# CN-Cape-1_1.net
KiCad netlist of a schematic drawn in EAGLE
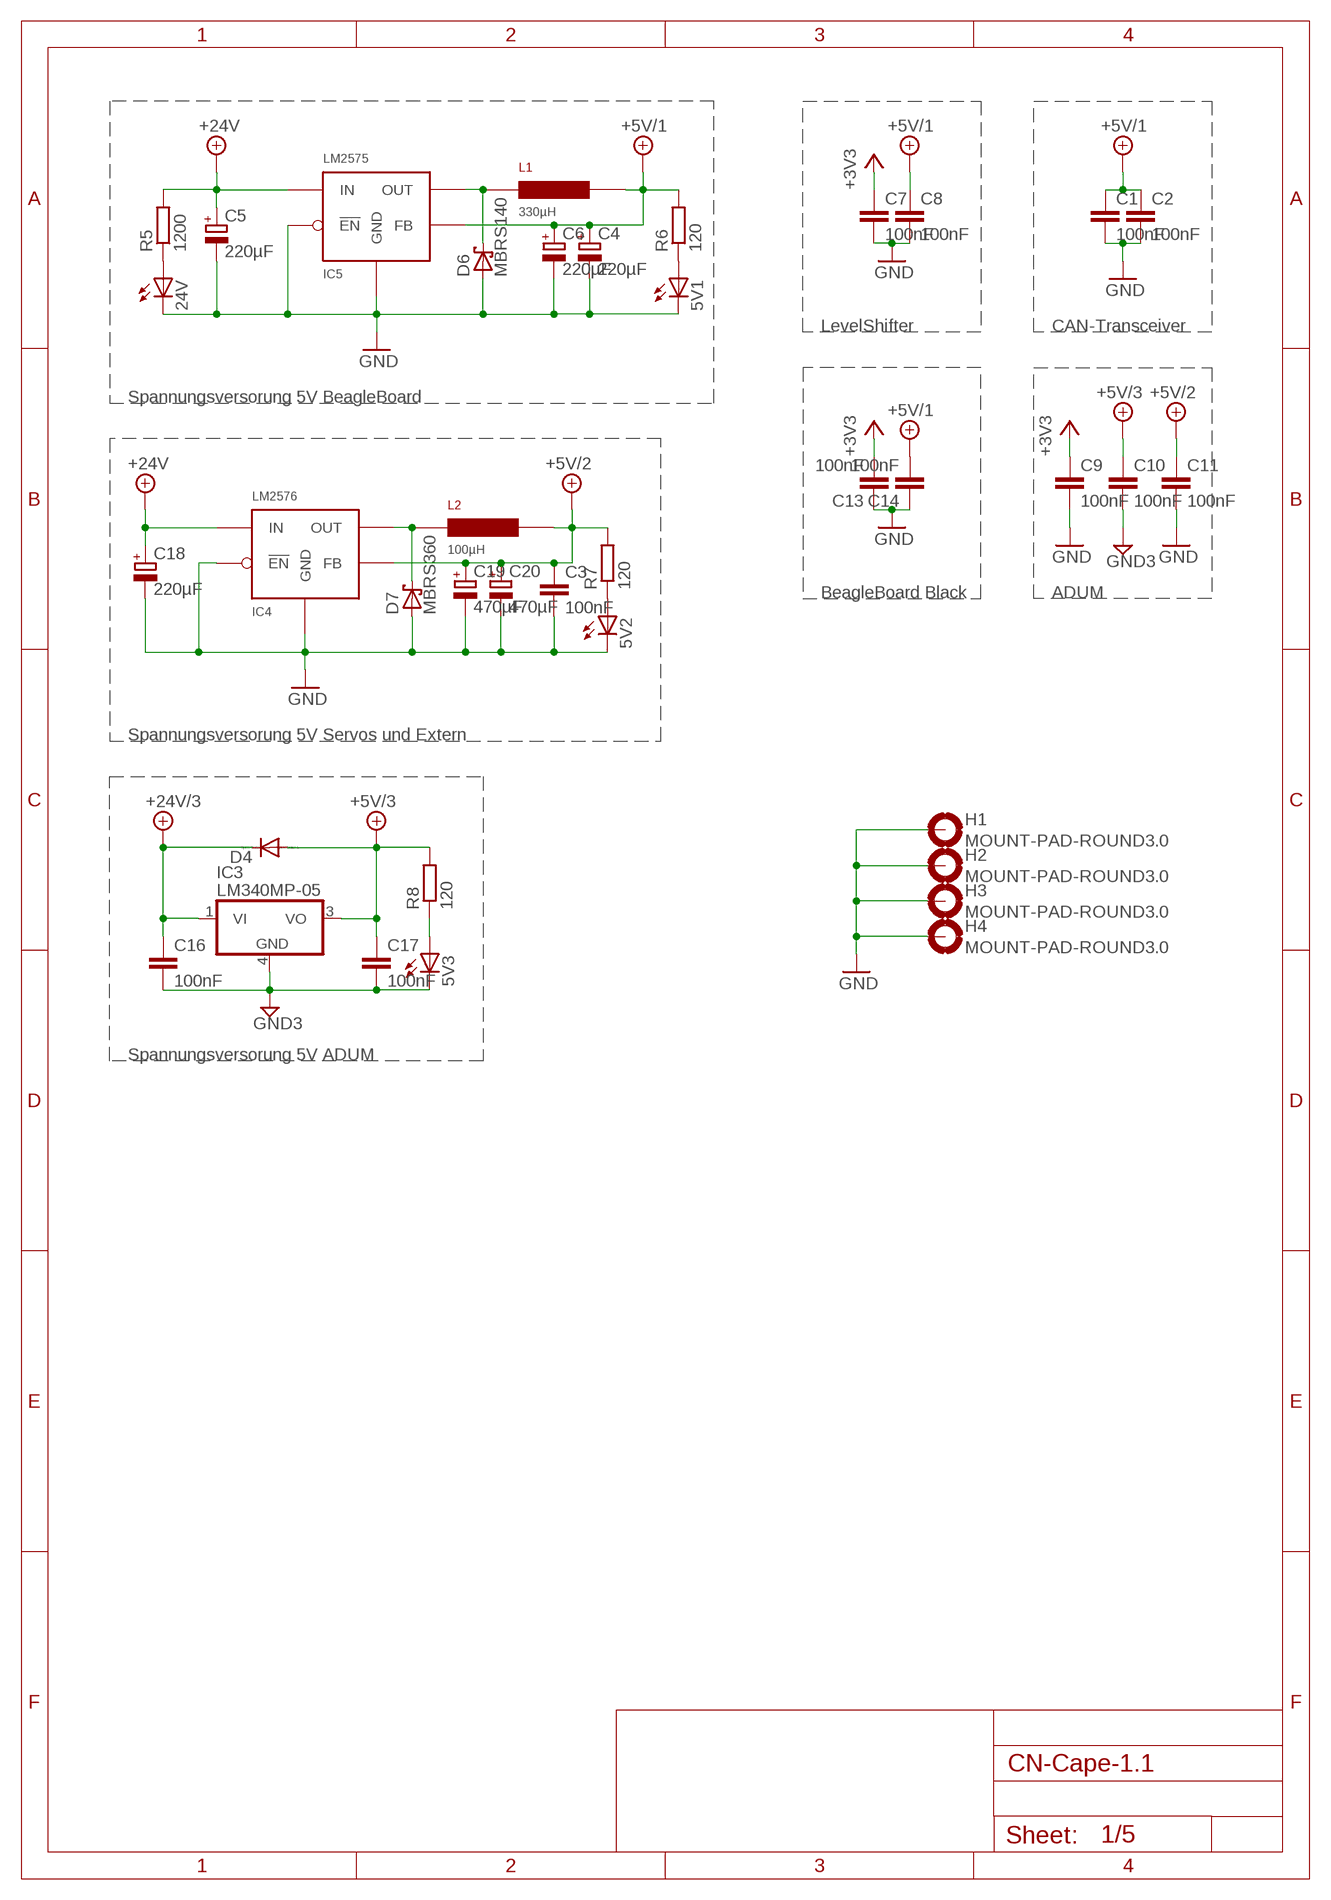
[diagram p0: schematic, sheet 1]
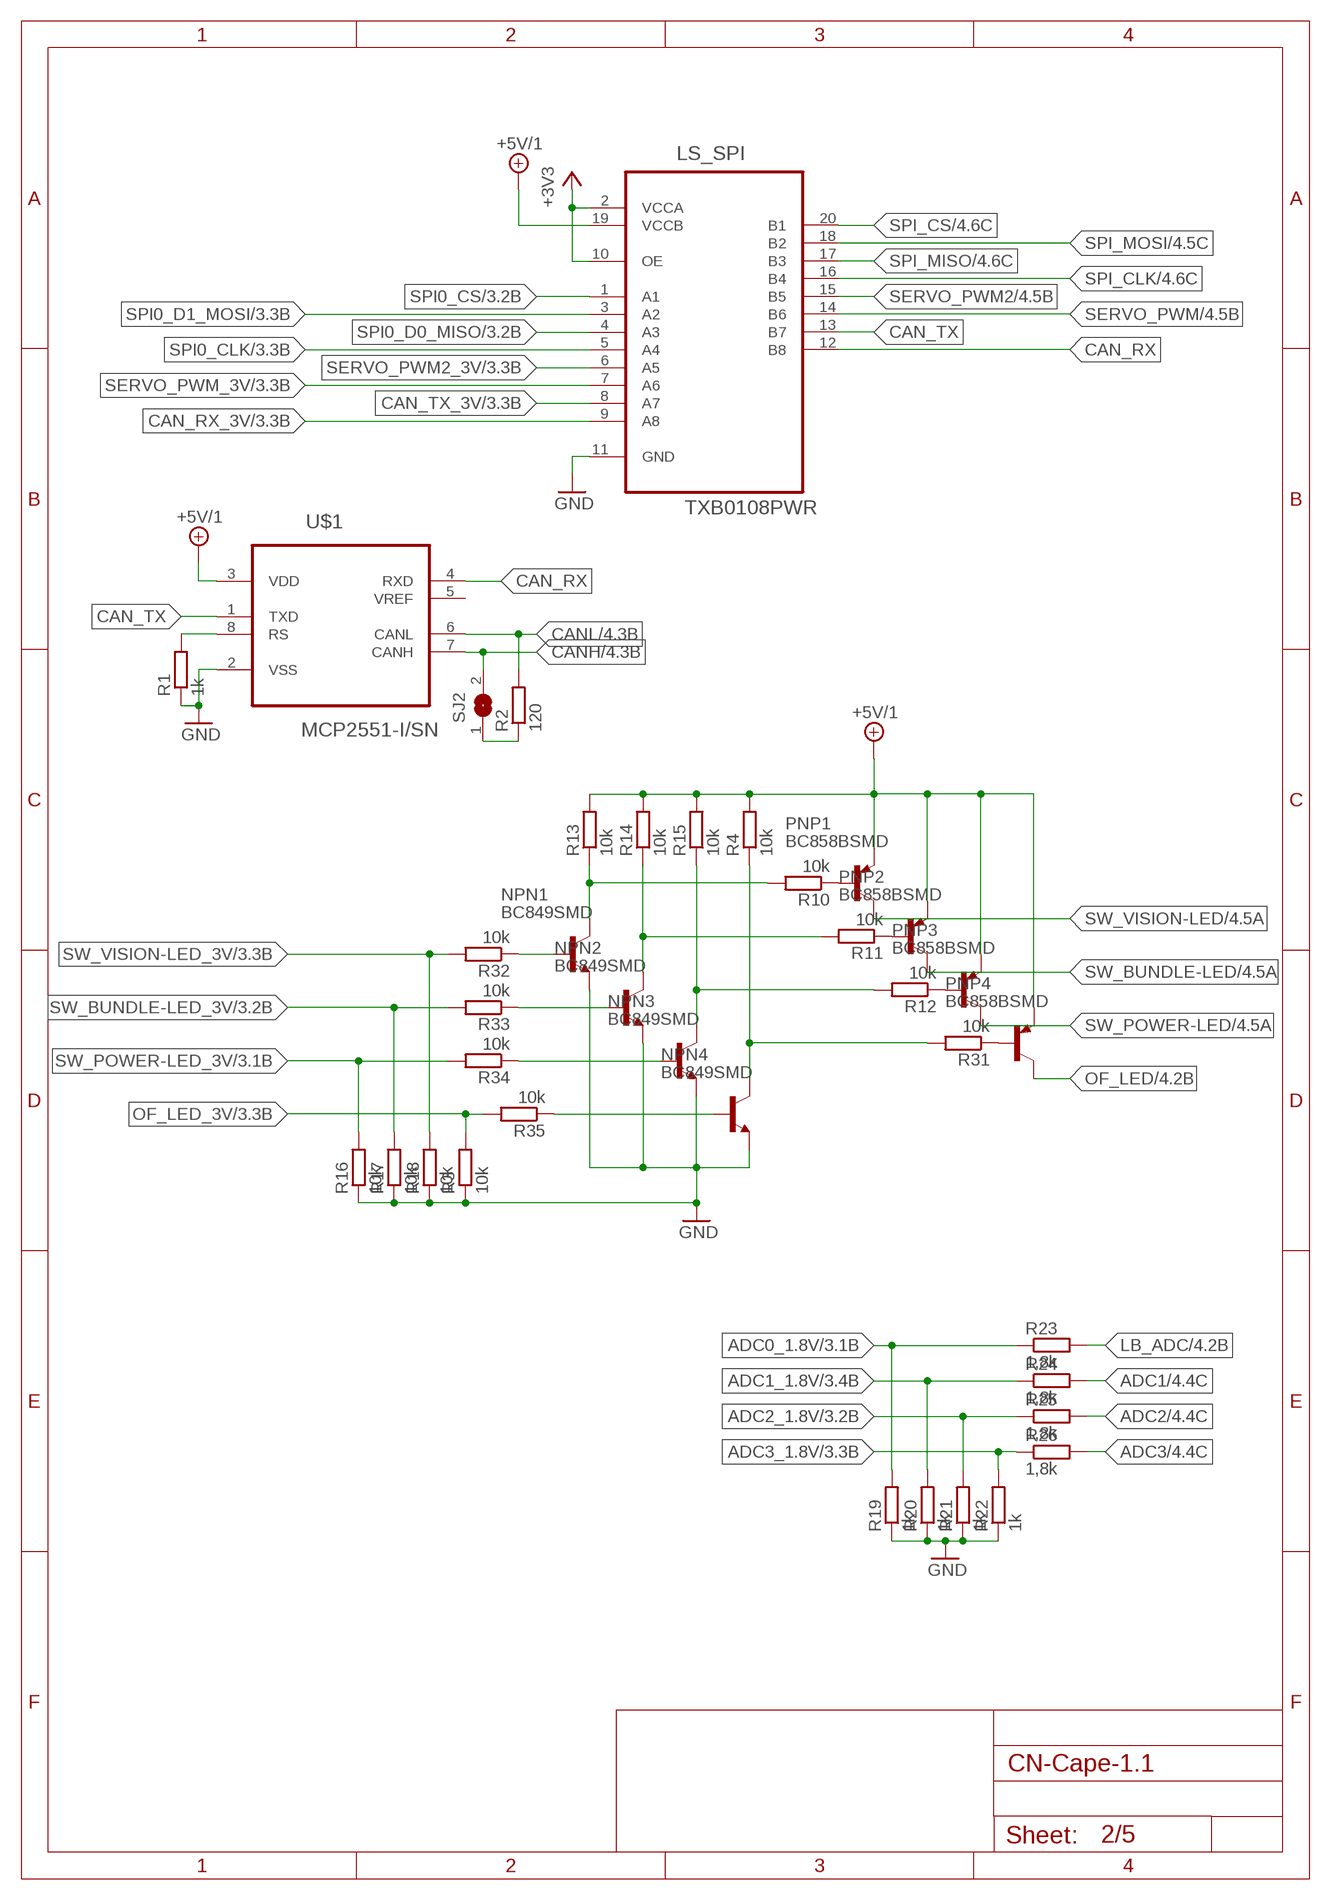
[diagram p1: schematic, sheet 2]
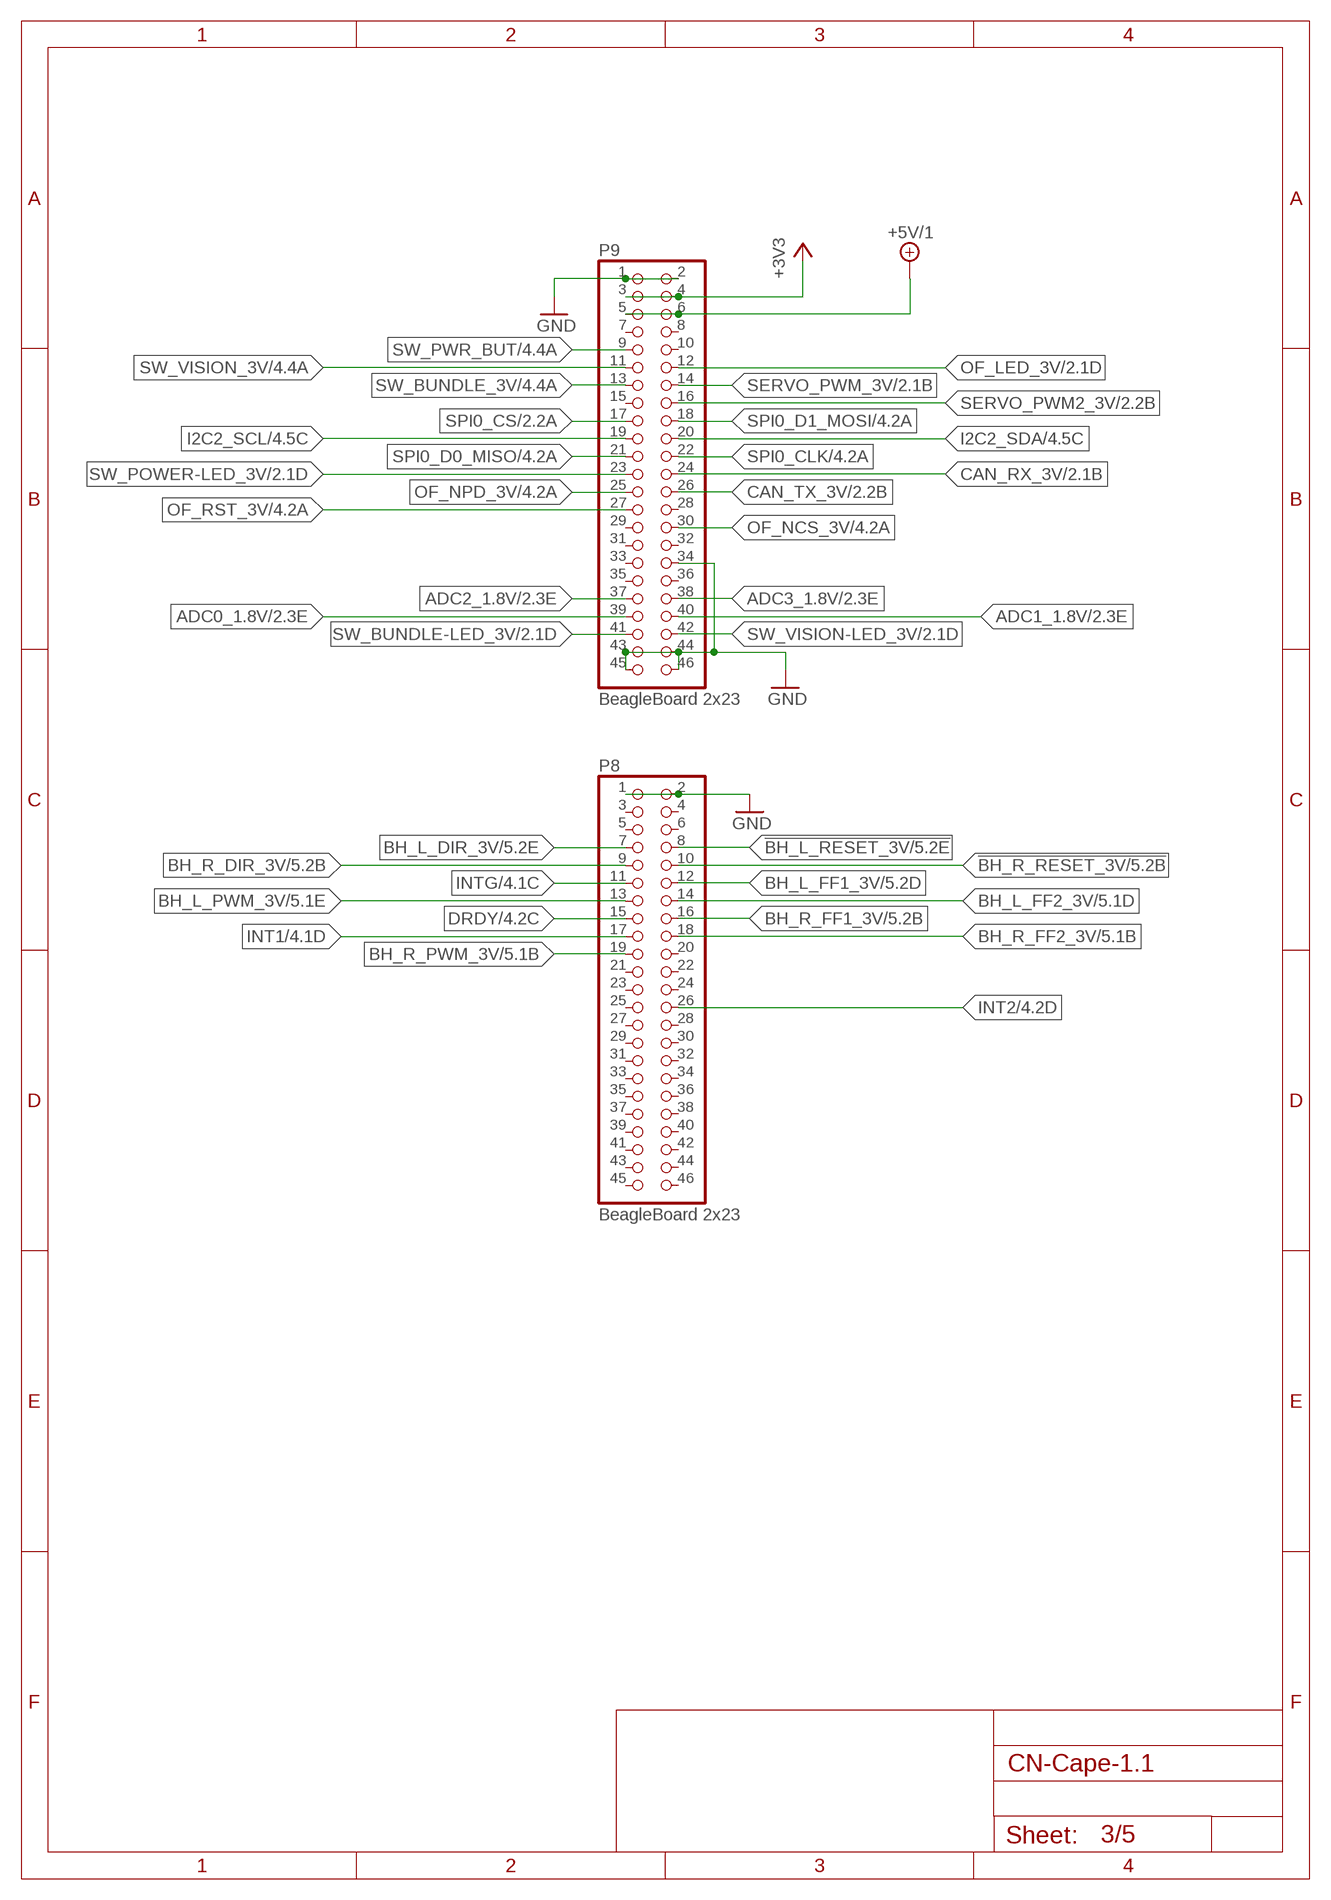
[diagram p2: schematic, sheet 3]
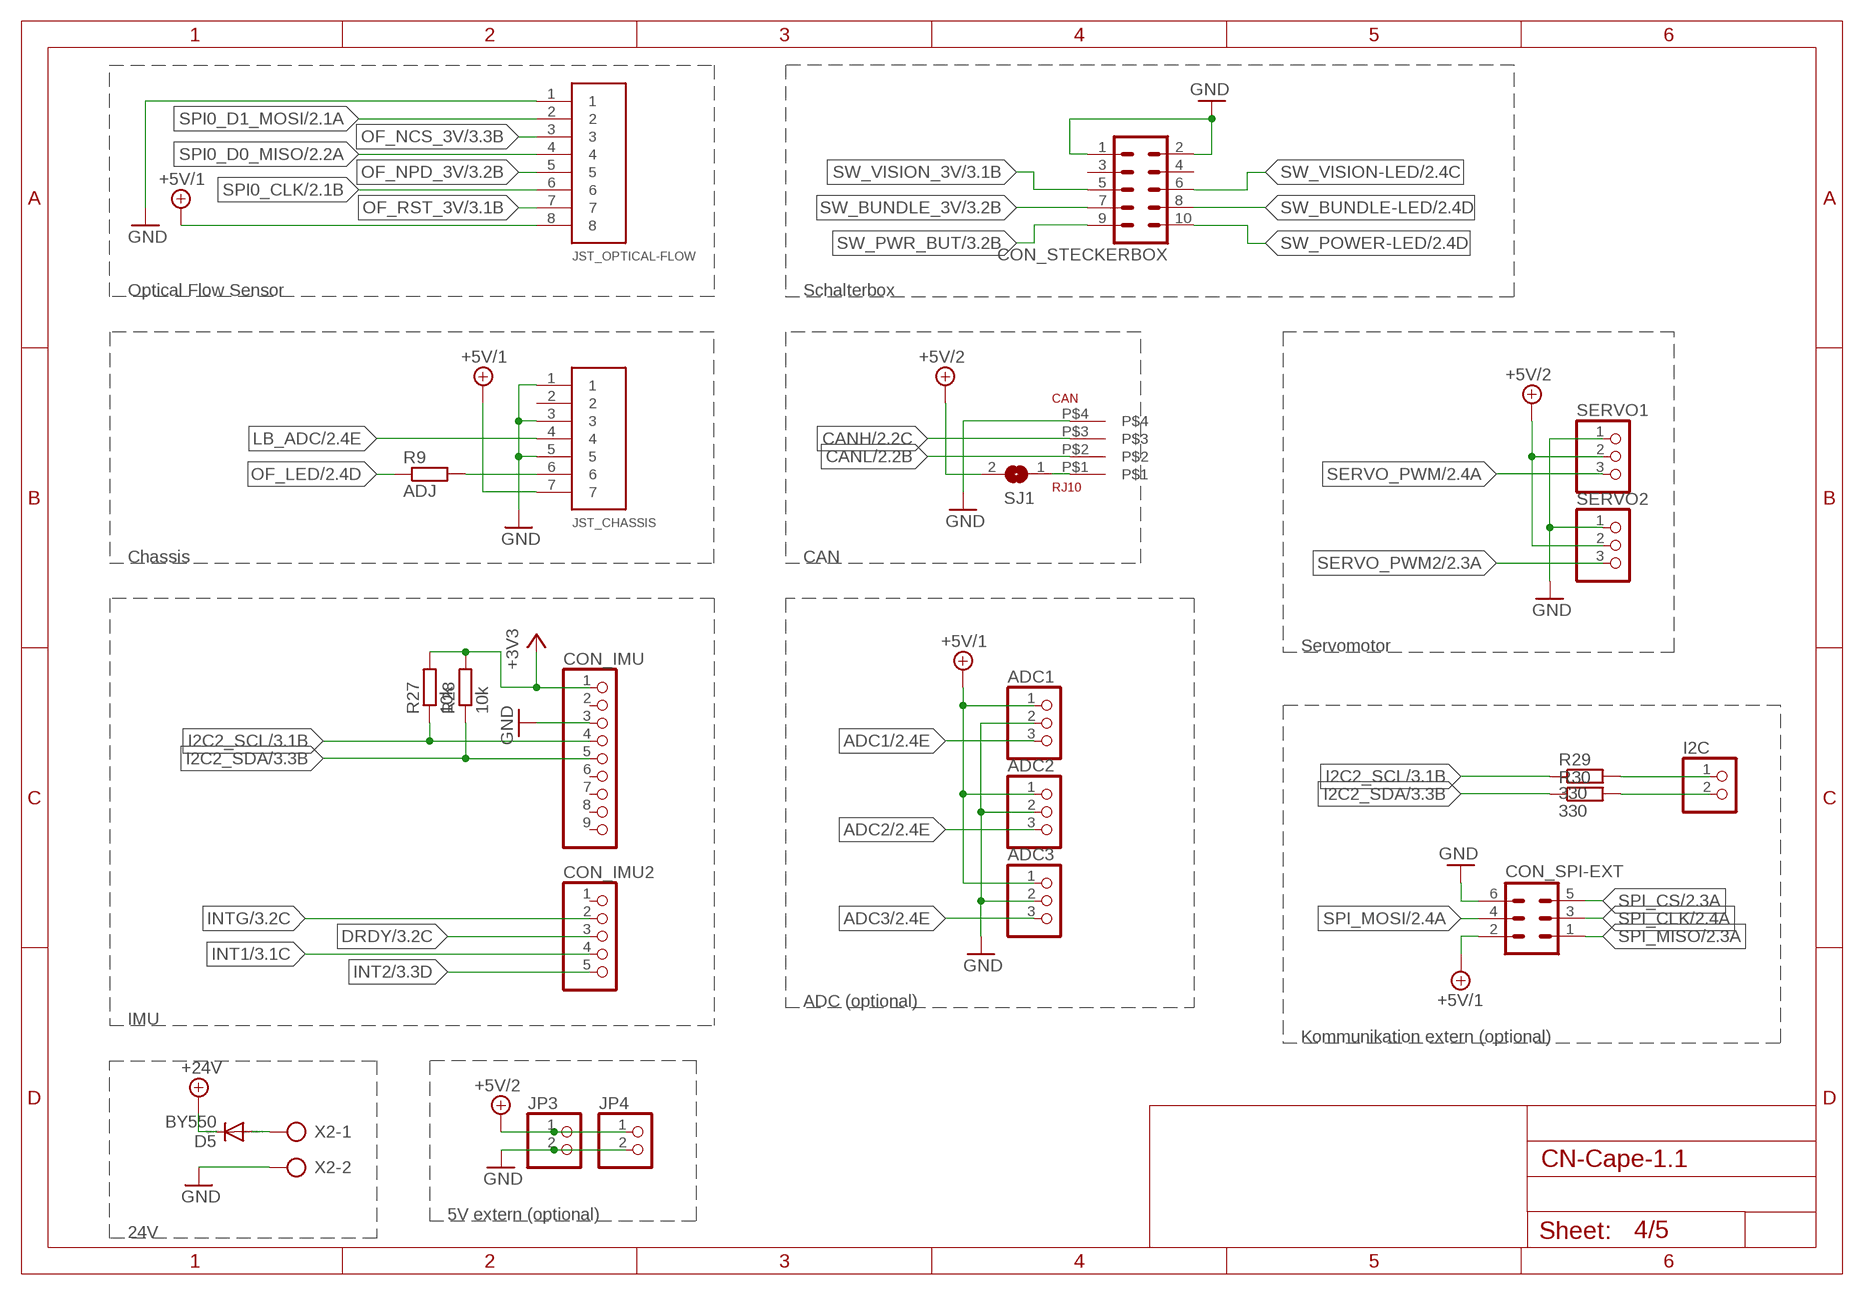
[diagram p3: schematic, sheet 4]
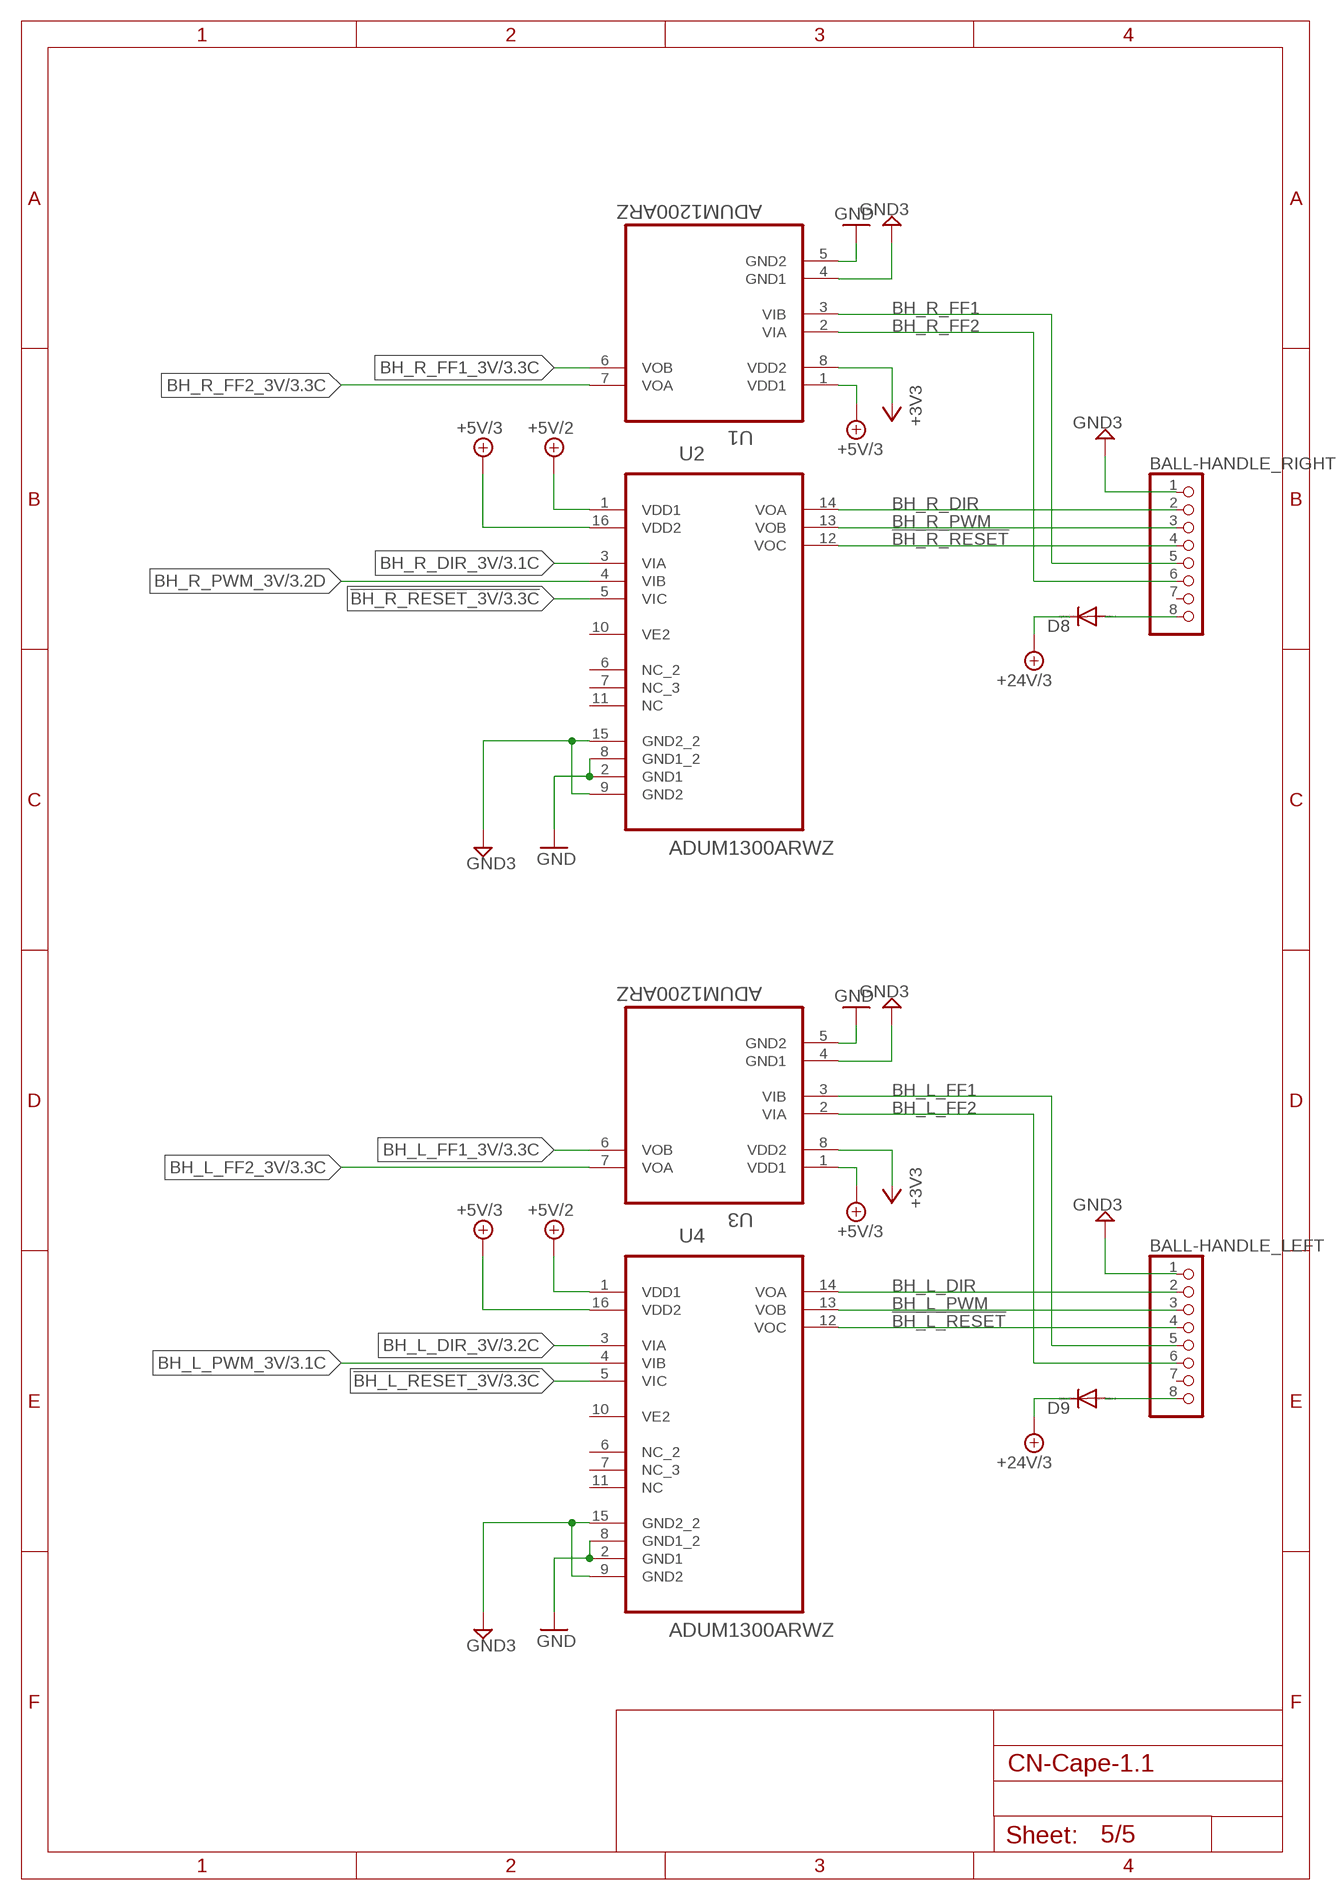
[diagram p4: schematic, sheet 5]

(export (version "E")
  (design (tool "Eeschema 10.0.6"))
  (components
    (comp (ref "LS_SPI")
      (value "TXB0108PWR")
      (footprint "eagle-import:SOP65P640X120-20N")
      (libsource (lib "eagle-import") (part "TXB0108PWR"))
    )
    (comp (ref "NPN1")
      (value "BC849SMD")
      (footprint "eagle-import:SOT23-BEC")
      (libsource (lib "eagle-import") (part "BC849SMD"))
    )
    (comp (ref "NPN2")
      (value "BC849SMD")
      (footprint "eagle-import:SOT23-BEC")
      (libsource (lib "eagle-import") (part "BC849SMD"))
    )
    (comp (ref "NPN3")
      (value "BC849SMD")
      (footprint "eagle-import:SOT23-BEC")
      (libsource (lib "eagle-import") (part "BC849SMD"))
    )
    (comp (ref "NPN4")
      (value "BC849SMD")
      (footprint "eagle-import:SOT23-BEC")
      (libsource (lib "eagle-import") (part "BC849SMD"))
    )
    (comp (ref "PNP1")
      (value "BC858BSMD")
      (footprint "eagle-import:SOT23-BEC")
      (libsource (lib "eagle-import") (part "BC858SMDB"))
    )
    (comp (ref "PNP2")
      (value "BC858BSMD")
      (footprint "eagle-import:SOT23-BEC")
      (libsource (lib "eagle-import") (part "BC858SMDB"))
    )
    (comp (ref "PNP3")
      (value "BC858BSMD")
      (footprint "eagle-import:SOT23-BEC")
      (libsource (lib "eagle-import") (part "BC858SMDB"))
    )
    (comp (ref "PNP4")
      (value "BC858BSMD")
      (footprint "eagle-import:SOT23-BEC")
      (libsource (lib "eagle-import") (part "BC858SMDB"))
    )
    (comp (ref "R1")
      (value "1k")
      (footprint "eagle-import:R0805")
      (libsource (lib "eagle-import") (part "R-EU_R0805"))
    )
    (comp (ref "R2")
      (value "120")
      (footprint "eagle-import:R0805")
      (libsource (lib "eagle-import") (part "R-EU_R0805"))
    )
    (comp (ref "R3")
      (value "10k")
      (footprint "eagle-import:R0805")
      (libsource (lib "eagle-import") (part "R-EU_R0805"))
    )
    (comp (ref "R4")
      (value "10k")
      (footprint "eagle-import:R0805")
      (libsource (lib "eagle-import") (part "R-EU_R0805"))
    )
    (comp (ref "R10")
      (value "10k")
      (footprint "eagle-import:R0805")
      (libsource (lib "eagle-import") (part "R-EU_R0805"))
    )
    (comp (ref "R11")
      (value "10k")
      (footprint "eagle-import:R0805")
      (libsource (lib "eagle-import") (part "R-EU_R0805"))
    )
    (comp (ref "R12")
      (value "10k")
      (footprint "eagle-import:R0805")
      (libsource (lib "eagle-import") (part "R-EU_R0805"))
    )
    (comp (ref "R13")
      (value "10k")
      (footprint "eagle-import:R0805")
      (libsource (lib "eagle-import") (part "R-EU_R0805"))
    )
    (comp (ref "R14")
      (value "10k")
      (footprint "eagle-import:R0805")
      (libsource (lib "eagle-import") (part "R-EU_R0805"))
    )
    (comp (ref "R15")
      (value "10k")
      (footprint "eagle-import:R0805")
      (libsource (lib "eagle-import") (part "R-EU_R0805"))
    )
    (comp (ref "R16")
      (value "10k")
      (footprint "eagle-import:R0805")
      (libsource (lib "eagle-import") (part "R-EU_R0805"))
    )
    (comp (ref "R17")
      (value "10k")
      (footprint "eagle-import:R0805")
      (libsource (lib "eagle-import") (part "R-EU_R0805"))
    )
    (comp (ref "R18")
      (value "10k")
      (footprint "eagle-import:R0805")
      (libsource (lib "eagle-import") (part "R-EU_R0805"))
    )
    (comp (ref "R19")
      (value "1k")
      (footprint "eagle-import:R0805")
      (libsource (lib "eagle-import") (part "R-EU_R0805"))
    )
    (comp (ref "R20")
      (value "1k")
      (footprint "eagle-import:R0805")
      (libsource (lib "eagle-import") (part "R-EU_R0805"))
    )
    (comp (ref "R21")
      (value "1k")
      (footprint "eagle-import:R0805")
      (libsource (lib "eagle-import") (part "R-EU_R0805"))
    )
    (comp (ref "R22")
      (value "1k")
      (footprint "eagle-import:R0805")
      (libsource (lib "eagle-import") (part "R-EU_R0805"))
    )
    (comp (ref "R23")
      (value "1,8k")
      (footprint "eagle-import:R0805")
      (libsource (lib "eagle-import") (part "R-EU_R0805"))
    )
    (comp (ref "R24")
      (value "1,8k")
      (footprint "eagle-import:R0805")
      (libsource (lib "eagle-import") (part "R-EU_R0805"))
    )
    (comp (ref "R25")
      (value "1,8k")
      (footprint "eagle-import:R0805")
      (libsource (lib "eagle-import") (part "R-EU_R0805"))
    )
    (comp (ref "R26")
      (value "1,8k")
      (footprint "eagle-import:R0805")
      (libsource (lib "eagle-import") (part "R-EU_R0805"))
    )
    (comp (ref "R31")
      (value "10k")
      (footprint "eagle-import:R0805")
      (libsource (lib "eagle-import") (part "R-EU_R0805"))
    )
    (comp (ref "R32")
      (value "10k")
      (footprint "eagle-import:R0805")
      (libsource (lib "eagle-import") (part "R-EU_R0805"))
    )
    (comp (ref "R33")
      (value "10k")
      (footprint "eagle-import:R0805")
      (libsource (lib "eagle-import") (part "R-EU_R0805"))
    )
    (comp (ref "R34")
      (value "10k")
      (footprint "eagle-import:R0805")
      (libsource (lib "eagle-import") (part "R-EU_R0805"))
    )
    (comp (ref "R35")
      (value "10k")
      (footprint "eagle-import:R0805")
      (libsource (lib "eagle-import") (part "R-EU_R0805"))
    )
    (comp (ref "SJ2") (value "SJ") (footprint "eagle-import:SJ") (libsource (lib "eagle-import") (part "SJ")))
    (comp (ref "U$1")
      (value "MCP2551-I/SN")
      (footprint "eagle-import:SOIC127P600X175-8N")
      (libsource (lib "eagle-import") (part "MCP2551-I/SN"))
    )
    (comp (ref "5V1")
      (value "LEDCHIP-LED0603")
      (footprint "eagle-import:CHIP-LED0603")
      (libsource (lib "eagle-import") (part "LEDCHIP-LED0603"))
    )
    (comp (ref "5V2")
      (value "LEDCHIP-LED0603")
      (footprint "eagle-import:CHIP-LED0603")
      (libsource (lib "eagle-import") (part "LEDCHIP-LED0603"))
    )
    (comp (ref "5V3")
      (value "LEDCHIP-LED0603")
      (footprint "eagle-import:CHIP-LED0603")
      (libsource (lib "eagle-import") (part "LEDCHIP-LED0603"))
    )
    (comp (ref "24V")
      (value "LEDCHIP-LED0603")
      (footprint "eagle-import:CHIP-LED0603")
      (libsource (lib "eagle-import") (part "LEDCHIP-LED0603"))
    )
    (comp (ref "C1")
      (value "100nF")
      (footprint "eagle-import:C0603")
      (libsource (lib "eagle-import") (part "C-EUC0603"))
    )
    (comp (ref "C2")
      (value "100nF")
      (footprint "eagle-import:C0603")
      (libsource (lib "eagle-import") (part "C-EUC0603"))
    )
    (comp (ref "C3")
      (value "100nF")
      (footprint "eagle-import:C0603")
      (libsource (lib "eagle-import") (part "C-EUC0603"))
    )
    (comp (ref "C4")
      (value "220µF")
      (footprint "eagle-import:E2,5-6")
      (libsource (lib "eagle-import") (part "CPOL-EUE2.5-6"))
    )
    (comp (ref "C5")
      (value "220µF")
      (footprint "eagle-import:E3,5-8")
      (libsource (lib "eagle-import") (part "CPOL-EUE3.5-8"))
    )
    (comp (ref "C6")
      (value "220µF")
      (footprint "eagle-import:E2,5-6")
      (libsource (lib "eagle-import") (part "CPOL-EUE2.5-6"))
    )
    (comp (ref "C7")
      (value "100nF")
      (footprint "eagle-import:C0603")
      (libsource (lib "eagle-import") (part "C-EUC0603"))
    )
    (comp (ref "C8")
      (value "100nF")
      (footprint "eagle-import:C0603")
      (libsource (lib "eagle-import") (part "C-EUC0603"))
    )
    (comp (ref "C9")
      (value "100nF")
      (footprint "eagle-import:C0603")
      (libsource (lib "eagle-import") (part "C-EUC0603"))
    )
    (comp (ref "C10")
      (value "100nF")
      (footprint "eagle-import:C0603")
      (libsource (lib "eagle-import") (part "C-EUC0603"))
    )
    (comp (ref "C11")
      (value "100nF")
      (footprint "eagle-import:C0603")
      (libsource (lib "eagle-import") (part "C-EUC0603"))
    )
    (comp (ref "C13")
      (value "100nF")
      (footprint "eagle-import:C0603")
      (libsource (lib "eagle-import") (part "C-EUC0603"))
    )
    (comp (ref "C14")
      (value "100nF")
      (footprint "eagle-import:C0603")
      (libsource (lib "eagle-import") (part "C-EUC0603"))
    )
    (comp (ref "C16")
      (value "100nF")
      (footprint "eagle-import:C0603")
      (libsource (lib "eagle-import") (part "C-EUC0603"))
    )
    (comp (ref "C17")
      (value "100nF")
      (footprint "eagle-import:C0603")
      (libsource (lib "eagle-import") (part "C-EUC0603"))
    )
    (comp (ref "C18")
      (value "220µF")
      (footprint "eagle-import:E3,5-8")
      (libsource (lib "eagle-import") (part "CPOL-EUE3.5-8"))
    )
    (comp (ref "C19")
      (value "470µF")
      (footprint "eagle-import:E3,5-8")
      (libsource (lib "eagle-import") (part "CPOL-EUE3.5-8"))
    )
    (comp (ref "C20")
      (value "470µF")
      (footprint "eagle-import:E3,5-8")
      (libsource (lib "eagle-import") (part "CPOL-EUE3.5-8"))
    )
    (comp (ref "D4")
      (value "DIODE-SOD123")
      (footprint "eagle-import:SOD123")
      (libsource (lib "eagle-import") (part "DIODE-SOD123"))
    )
    (comp (ref "D6")
      (value "MBRS140")
      (footprint "eagle-import:SMB")
      (libsource (lib "eagle-import") (part "MBRS130LT3"))
    )
    (comp (ref "D7")
      (value "MBRS360")
      (footprint "eagle-import:SMC")
      (libsource (lib "eagle-import") (part "MBRS30T34"))
    )
    (comp (ref "H1")
      (value "MOUNT-PAD-ROUND3.0")
      (footprint "eagle-import:3,0-PAD")
      (libsource (lib "eagle-import") (part "MOUNT-PAD-ROUND3.0"))
    )
    (comp (ref "H2")
      (value "MOUNT-PAD-ROUND3.0")
      (footprint "eagle-import:3,0-PAD")
      (libsource (lib "eagle-import") (part "MOUNT-PAD-ROUND3.0"))
    )
    (comp (ref "H3")
      (value "MOUNT-PAD-ROUND3.0")
      (footprint "eagle-import:3,0-PAD")
      (libsource (lib "eagle-import") (part "MOUNT-PAD-ROUND3.0"))
    )
    (comp (ref "H4")
      (value "MOUNT-PAD-ROUND3.0")
      (footprint "eagle-import:3,0-PAD")
      (libsource (lib "eagle-import") (part "MOUNT-PAD-ROUND3.0"))
    )
    (comp (ref "IC3")
      (value "LM340MP-05")
      (footprint "eagle-import:SOT223")
      (libsource (lib "eagle-import") (part "LM340?-MP05"))
    )
    (comp (ref "IC4")
      (value "LM2576")
      (footprint "eagle-import:TO220-5_STAGGERED")
      (libsource (lib "eagle-import") (part "LM2576-T05D"))
    )
    (comp (ref "IC5")
      (value "LM2575")
      (footprint "eagle-import:TO220-5_STAGGERED")
      (libsource (lib "eagle-import") (part "LM2576-T05D"))
    )
    (comp (ref "L1")
      (value "330µH")
      (footprint "eagle-import:PISR")
      (libsource (lib "eagle-import") (part "PISR"))
    )
    (comp (ref "L2")
      (value "100µH")
      (footprint "eagle-import:PISR")
      (libsource (lib "eagle-import") (part "PISR"))
    )
    (comp (ref "R5")
      (value "1200")
      (footprint "eagle-import:R0805")
      (libsource (lib "eagle-import") (part "R-EU_R0805"))
    )
    (comp (ref "R6")
      (value "120")
      (footprint "eagle-import:R0805")
      (libsource (lib "eagle-import") (part "R-EU_R0805"))
    )
    (comp (ref "R7")
      (value "120")
      (footprint "eagle-import:R0805")
      (libsource (lib "eagle-import") (part "R-EU_R0805"))
    )
    (comp (ref "R8")
      (value "120")
      (footprint "eagle-import:R0805")
      (libsource (lib "eagle-import") (part "R-EU_R0805"))
    )
    (comp (ref "ADC1")
      (value "PINHD-1X3")
      (footprint "eagle-import:1X03")
      (libsource (lib "eagle-import") (part "PINHD-1X3"))
    )
    (comp (ref "ADC2")
      (value "PINHD-1X3")
      (footprint "eagle-import:1X03")
      (libsource (lib "eagle-import") (part "PINHD-1X3"))
    )
    (comp (ref "ADC3")
      (value "PINHD-1X3")
      (footprint "eagle-import:1X03")
      (libsource (lib "eagle-import") (part "PINHD-1X3"))
    )
    (comp (ref "CAN")
      (value "RJ10")
      (footprint "eagle-import:RJ10")
      (libsource (lib "eagle-import") (part "RJ10"))
    )
    (comp (ref "CON_IMU")
      (value "PINHD-1X9")
      (footprint "eagle-import:1X09")
      (libsource (lib "eagle-import") (part "PINHD-1X9"))
    )
    (comp (ref "CON_IMU2")
      (value "PINHD-1X5")
      (footprint "eagle-import:1X05")
      (libsource (lib "eagle-import") (part "PINHD-1X5"))
    )
    (comp (ref "CON_SPI-EXT")
      (value "ML6")
      (footprint "eagle-import:ML6")
      (libsource (lib "eagle-import") (part "ML6"))
    )
    (comp (ref "CON_STECKERBOX")
      (value "ML10")
      (footprint "eagle-import:ML10")
      (libsource (lib "eagle-import") (part "ML10"))
    )
    (comp (ref "D5")
      (value "BY550")
      (footprint "eagle-import:DO27-15")
      (libsource (lib "eagle-import") (part "BY550"))
    )
    (comp (ref "I2C")
      (value "PINHD-1X2")
      (footprint "eagle-import:1X02")
      (libsource (lib "eagle-import") (part "PINHD-1X2"))
    )
    (comp (ref "JP3")
      (value "PINHD-1X2")
      (footprint "eagle-import:1X02")
      (libsource (lib "eagle-import") (part "PINHD-1X2"))
    )
    (comp (ref "JP4")
      (value "PINHD-1X2")
      (footprint "eagle-import:1X02")
      (libsource (lib "eagle-import") (part "PINHD-1X2"))
    )
    (comp (ref "JST_CHASSIS")
      (value "S7PIN")
      (footprint "eagle-import:S7B-EH")
      (libsource (lib "eagle-import") (part "S7PIN"))
    )
    (comp (ref "JST_OPTICAL-FLOW")
      (value "S8PIN")
      (footprint "eagle-import:S8B-EH")
      (libsource (lib "eagle-import") (part "S8PIN"))
    )
    (comp (ref "R9")
      (value "ADJ")
      (footprint "eagle-import:R0805")
      (libsource (lib "eagle-import") (part "R-EU_R0805"))
    )
    (comp (ref "R27")
      (value "10k")
      (footprint "eagle-import:R0805")
      (libsource (lib "eagle-import") (part "R-EU_R0805"))
    )
    (comp (ref "R28")
      (value "10k")
      (footprint "eagle-import:R0805")
      (libsource (lib "eagle-import") (part "R-EU_R0805"))
    )
    (comp (ref "R29")
      (value "330")
      (footprint "eagle-import:R0805")
      (libsource (lib "eagle-import") (part "R-EU_R0805"))
    )
    (comp (ref "R30")
      (value "330")
      (footprint "eagle-import:R0805")
      (libsource (lib "eagle-import") (part "R-EU_R0805"))
    )
    (comp (ref "SERVO1")
      (value "PINHD-1X3")
      (footprint "eagle-import:1X03")
      (libsource (lib "eagle-import") (part "PINHD-1X3"))
    )
    (comp (ref "SERVO2")
      (value "PINHD-1X3")
      (footprint "eagle-import:1X03")
      (libsource (lib "eagle-import") (part "PINHD-1X3"))
    )
    (comp (ref "SJ1") (value "SJ") (footprint "eagle-import:SJ") (libsource (lib "eagle-import") (part "SJ")))
    (comp (ref "X2")
      (value "AK500/2-H")
      (footprint "eagle-import:AK500_2-H")
      (libsource (lib "eagle-import") (part "AK500/2-H"))
    )
    (comp (ref "BALL-HANDLE_LEFT")
      (value "PINHD-1X8")
      (footprint "eagle-import:1X08")
      (libsource (lib "eagle-import") (part "PINHD-1X8"))
    )
    (comp (ref "BALL-HANDLE_RIGHT")
      (value "PINHD-1X8")
      (footprint "eagle-import:1X08")
      (libsource (lib "eagle-import") (part "PINHD-1X8"))
    )
    (comp (ref "D8")
      (value "DIODE-SOD123")
      (footprint "eagle-import:SOD123")
      (libsource (lib "eagle-import") (part "DIODE-SOD123"))
    )
    (comp (ref "D9")
      (value "DIODE-SOD123")
      (footprint "eagle-import:SOD123")
      (libsource (lib "eagle-import") (part "DIODE-SOD123"))
    )
    (comp (ref "U1")
      (value "ADUM1200ARZ")
      (footprint "eagle-import:SOIC127P600X175-8N")
      (libsource (lib "eagle-import") (part "ADUM1200ARZ"))
    )
    (comp (ref "U2")
      (value "ADUM1300ARWZ")
      (footprint "eagle-import:SOIC127P1032X265-16N")
      (libsource (lib "eagle-import") (part "ADUM1300ARWZ"))
    )
    (comp (ref "U3")
      (value "ADUM1200ARZ")
      (footprint "eagle-import:SOIC127P600X175-8N")
      (libsource (lib "eagle-import") (part "ADUM1200ARZ"))
    )
    (comp (ref "U4")
      (value "ADUM1300ARWZ")
      (footprint "eagle-import:SOIC127P1032X265-16N")
      (libsource (lib "eagle-import") (part "ADUM1300ARWZ"))
    )
    (comp (ref "P8")
      (value "BeagleBoard 2x23")
      (footprint "eagle-import:2X23")
      (libsource (lib "eagle-import") (part "PINHD-2X23"))
    )
    (comp (ref "P9")
      (value "BeagleBoard 2x23")
      (footprint "eagle-import:2X23")
      (libsource (lib "eagle-import") (part "PINHD-2X23"))
    )
  )
  (nets
    (net (code "1") (name "+3V3") (class "Default")
      (node (ref "C13") (pin "2") (pinfunction "2_2") (pintype "passive"))
      (node (ref "C7") (pin "1") (pinfunction "1_1") (pintype "passive"))
      (node (ref "C9") (pin "1") (pinfunction "1_1") (pintype "passive"))
      (node (ref "CON_IMU") (pin "1") (pinfunction "1_1") (pintype "passive"))
      (node (ref "LS_SPI") (pin "10") (pinfunction "OE_10") (pintype "input"))
      (node (ref "LS_SPI") (pin "2") (pinfunction "VCCA_2") (pintype "power_in"))
      (node (ref "P9") (pin "3") (pinfunction "3_3") (pintype "passive"))
      (node (ref "P9") (pin "4") (pinfunction "4_4") (pintype "passive"))
      (node (ref "R27") (pin "2") (pinfunction "2_2") (pintype "passive"))
      (node (ref "R28") (pin "2") (pinfunction "2_2") (pintype "passive"))
      (node (ref "U1") (pin "8") (pinfunction "VDD2_8") (pintype "power_in"))
      (node (ref "U3") (pin "8") (pinfunction "VDD2_8") (pintype "power_in"))
    )
    (net (code "2") (name "+5V{slash}1") (class "Default")
      (node (ref "ADC1") (pin "1") (pinfunction "1_1") (pintype "passive"))
      (node (ref "ADC2") (pin "1") (pinfunction "1_1") (pintype "passive"))
      (node (ref "ADC3") (pin "1") (pinfunction "1_1") (pintype "passive"))
      (node (ref "C1") (pin "1") (pinfunction "1_1") (pintype "passive"))
      (node (ref "C14") (pin "2") (pinfunction "2_2") (pintype "passive"))
      (node (ref "C2") (pin "1") (pinfunction "1_1") (pintype "passive"))
      (node (ref "C4") (pin "+") (pinfunction "+_+") (pintype "passive"))
      (node (ref "C6") (pin "+") (pinfunction "+_+") (pintype "passive"))
      (node (ref "C8") (pin "1") (pinfunction "1_1") (pintype "passive"))
      (node (ref "CON_SPI-EXT") (pin "2") (pinfunction "2_2") (pintype "passive"))
      (node (ref "IC5") (pin "FB") (pinfunction "FB_FB") (pintype "input"))
      (node (ref "JST_CHASSIS") (pin "7") (pinfunction "7_7") (pintype "bidirectional"))
      (node (ref "JST_OPTICAL-FLOW") (pin "8") (pinfunction "8_8") (pintype "bidirectional"))
      (node (ref "L1") (pin "P$2") (pinfunction "P$2_P$2") (pintype "bidirectional"))
      (node (ref "LS_SPI") (pin "19") (pinfunction "VCCB_19") (pintype "power_in"))
      (node (ref "P9") (pin "5") (pinfunction "5_5") (pintype "passive"))
      (node (ref "P9") (pin "6") (pinfunction "6_6") (pintype "passive"))
      (node (ref "PNP1") (pin "E") (pinfunction "E_E") (pintype "passive"))
      (node (ref "PNP2") (pin "E") (pinfunction "E_E") (pintype "passive"))
      (node (ref "PNP3") (pin "E") (pinfunction "E_E") (pintype "passive"))
      (node (ref "PNP4") (pin "E") (pinfunction "E_E") (pintype "passive"))
      (node (ref "R13") (pin "2") (pinfunction "2_2") (pintype "passive"))
      (node (ref "R14") (pin "2") (pinfunction "2_2") (pintype "passive"))
      (node (ref "R15") (pin "2") (pinfunction "2_2") (pintype "passive"))
      (node (ref "R4") (pin "2") (pinfunction "2_2") (pintype "passive"))
      (node (ref "R6") (pin "2") (pinfunction "2_2") (pintype "passive"))
      (node (ref "U$1") (pin "3") (pinfunction "VDD_3") (pintype "power_in"))
    )
    (net (code "3") (name "+5V{slash}2") (class "Default")
      (node (ref "C11") (pin "1") (pinfunction "1_1") (pintype "passive"))
      (node (ref "C19") (pin "+") (pinfunction "+_+") (pintype "passive"))
      (node (ref "C20") (pin "+") (pinfunction "+_+") (pintype "passive"))
      (node (ref "C3") (pin "1") (pinfunction "1_1") (pintype "passive"))
      (node (ref "IC4") (pin "FB") (pinfunction "FB_FB") (pintype "input"))
      (node (ref "JP3") (pin "1") (pinfunction "1_1") (pintype "passive"))
      (node (ref "JP4") (pin "1") (pinfunction "1_1") (pintype "passive"))
      (node (ref "L2") (pin "P$2") (pinfunction "P$2_P$2") (pintype "bidirectional"))
      (node (ref "R7") (pin "2") (pinfunction "2_2") (pintype "passive"))
      (node (ref "SERVO1") (pin "2") (pinfunction "2_2") (pintype "passive"))
      (node (ref "SERVO2") (pin "2") (pinfunction "2_2") (pintype "passive"))
      (node (ref "SJ1") (pin "2") (pinfunction "2_2") (pintype "passive"))
      (node (ref "U2") (pin "1") (pinfunction "VDD1_1") (pintype "power_in"))
      (node (ref "U4") (pin "1") (pinfunction "VDD1_1") (pintype "power_in"))
    )
    (net (code "4") (name "+5V{slash}3") (class "Default")
      (node (ref "C10") (pin "1") (pinfunction "1_1") (pintype "passive"))
      (node (ref "C17") (pin "1") (pinfunction "1_1") (pintype "passive"))
      (node (ref "D4") (pin "A") (pinfunction "A_A") (pintype "passive"))
      (node (ref "IC3") (pin "3") (pinfunction "VO_3") (pintype "passive"))
      (node (ref "R8") (pin "2") (pinfunction "2_2") (pintype "passive"))
      (node (ref "U1") (pin "1") (pinfunction "VDD1_1") (pintype "power_in"))
      (node (ref "U2") (pin "16") (pinfunction "VDD2_16") (pintype "power_in"))
      (node (ref "U3") (pin "1") (pinfunction "VDD1_1") (pintype "power_in"))
      (node (ref "U4") (pin "16") (pinfunction "VDD2_16") (pintype "power_in"))
    )
    (net (code "5") (name "+24V") (class "Default")
      (node (ref "C18") (pin "+") (pinfunction "+_+") (pintype "passive"))
      (node (ref "C5") (pin "+") (pinfunction "+_+") (pintype "passive"))
      (node (ref "D5") (pin "C") (pinfunction "C_C") (pintype "passive"))
      (node (ref "IC4") (pin "IN") (pinfunction "IN_IN") (pintype "input"))
      (node (ref "IC5") (pin "IN") (pinfunction "IN_IN") (pintype "input"))
      (node (ref "R5") (pin "2") (pinfunction "2_2") (pintype "passive"))
    )
    (net (code "6") (name "+24V{slash}3") (class "Default")
      (node (ref "C16") (pin "1") (pinfunction "1_1") (pintype "passive"))
      (node (ref "D4") (pin "C") (pinfunction "C_C") (pintype "passive"))
      (node (ref "D8") (pin "C") (pinfunction "C_C") (pintype "passive"))
      (node (ref "D9") (pin "C") (pinfunction "C_C") (pintype "passive"))
      (node (ref "IC3") (pin "1") (pinfunction "VI_1") (pintype "input"))
    )
    (net (code "7") (name "ADC0_1.8V") (class "Default")
      (node (ref "P9") (pin "39") (pinfunction "39_39") (pintype "passive"))
      (node (ref "R19") (pin "2") (pinfunction "2_2") (pintype "passive"))
      (node (ref "R23") (pin "1") (pinfunction "1_1") (pintype "passive"))
    )
    (net (code "8") (name "ADC1") (class "Default")
      (node (ref "ADC1") (pin "3") (pinfunction "3_3") (pintype "passive"))
      (node (ref "R24") (pin "2") (pinfunction "2_2") (pintype "passive"))
    )
    (net (code "9") (name "ADC1_1.8V") (class "Default")
      (node (ref "P9") (pin "40") (pinfunction "40_40") (pintype "passive"))
      (node (ref "R20") (pin "2") (pinfunction "2_2") (pintype "passive"))
      (node (ref "R24") (pin "1") (pinfunction "1_1") (pintype "passive"))
    )
    (net (code "10") (name "ADC2") (class "Default")
      (node (ref "ADC2") (pin "3") (pinfunction "3_3") (pintype "passive"))
      (node (ref "R25") (pin "2") (pinfunction "2_2") (pintype "passive"))
    )
    (net (code "11") (name "ADC2_1.8V") (class "Default")
      (node (ref "P9") (pin "37") (pinfunction "37_37") (pintype "passive"))
      (node (ref "R21") (pin "2") (pinfunction "2_2") (pintype "passive"))
      (node (ref "R25") (pin "1") (pinfunction "1_1") (pintype "passive"))
    )
    (net (code "12") (name "ADC3") (class "Default")
      (node (ref "ADC3") (pin "3") (pinfunction "3_3") (pintype "passive"))
      (node (ref "R26") (pin "2") (pinfunction "2_2") (pintype "passive"))
    )
    (net (code "13") (name "ADC3_1.8V") (class "Default")
      (node (ref "P9") (pin "38") (pinfunction "38_38") (pintype "passive"))
      (node (ref "R22") (pin "2") (pinfunction "2_2") (pintype "passive"))
      (node (ref "R26") (pin "1") (pinfunction "1_1") (pintype "passive"))
    )
    (net (code "14") (name "BH_L_DIR") (class "Default")
      (node (ref "BALL-HANDLE_LEFT") (pin "2") (pinfunction "2_2") (pintype "passive"))
      (node (ref "U4") (pin "14") (pinfunction "VOA_14") (pintype "output"))
    )
    (net (code "15") (name "BH_L_DIR_3V") (class "Default")
      (node (ref "P8") (pin "7") (pinfunction "7_7") (pintype "passive"))
      (node (ref "U4") (pin "3") (pinfunction "VIA_3") (pintype "input"))
    )
    (net (code "16") (name "BH_L_FF1") (class "Default")
      (node (ref "BALL-HANDLE_LEFT") (pin "5") (pinfunction "5_5") (pintype "passive"))
      (node (ref "U3") (pin "3") (pinfunction "VIB_3") (pintype "input"))
    )
    (net (code "17") (name "BH_L_FF1_3V") (class "Default")
      (node (ref "P8") (pin "12") (pinfunction "12_12") (pintype "passive"))
      (node (ref "U3") (pin "6") (pinfunction "VOB_6") (pintype "output"))
    )
    (net (code "18") (name "BH_L_FF2") (class "Default")
      (node (ref "BALL-HANDLE_LEFT") (pin "6") (pinfunction "6_6") (pintype "passive"))
      (node (ref "U3") (pin "2") (pinfunction "VIA_2") (pintype "input"))
    )
    (net (code "19") (name "BH_L_FF2_3V") (class "Default")
      (node (ref "P8") (pin "14") (pinfunction "14_14") (pintype "passive"))
      (node (ref "U3") (pin "7") (pinfunction "VOA_7") (pintype "output"))
    )
    (net (code "20") (name "BH_L_PWM") (class "Default")
      (node (ref "BALL-HANDLE_LEFT") (pin "3") (pinfunction "3_3") (pintype "passive"))
      (node (ref "U4") (pin "13") (pinfunction "VOB_13") (pintype "output"))
    )
    (net (code "21") (name "BH_L_PWM_3V") (class "Default")
      (node (ref "P8") (pin "13") (pinfunction "13_13") (pintype "passive"))
      (node (ref "U4") (pin "4") (pinfunction "VIB_4") (pintype "input"))
    )
    (net (code "22") (name "BH_R_DIR") (class "Default")
      (node (ref "BALL-HANDLE_RIGHT") (pin "2") (pinfunction "2_2") (pintype "passive"))
      (node (ref "U2") (pin "14") (pinfunction "VOA_14") (pintype "output"))
    )
    (net (code "23") (name "BH_R_DIR_3V") (class "Default")
      (node (ref "P8") (pin "9") (pinfunction "9_9") (pintype "passive"))
      (node (ref "U2") (pin "3") (pinfunction "VIA_3") (pintype "input"))
    )
    (net (code "24") (name "BH_R_FF1") (class "Default")
      (node (ref "BALL-HANDLE_RIGHT") (pin "5") (pinfunction "5_5") (pintype "passive"))
      (node (ref "U1") (pin "3") (pinfunction "VIB_3") (pintype "input"))
    )
    (net (code "25") (name "BH_R_FF1_3V") (class "Default")
      (node (ref "P8") (pin "16") (pinfunction "16_16") (pintype "passive"))
      (node (ref "U1") (pin "6") (pinfunction "VOB_6") (pintype "output"))
    )
    (net (code "26") (name "BH_R_FF2") (class "Default")
      (node (ref "BALL-HANDLE_RIGHT") (pin "6") (pinfunction "6_6") (pintype "passive"))
      (node (ref "U1") (pin "2") (pinfunction "VIA_2") (pintype "input"))
    )
    (net (code "27") (name "BH_R_FF2_3V") (class "Default")
      (node (ref "P8") (pin "18") (pinfunction "18_18") (pintype "passive"))
      (node (ref "U1") (pin "7") (pinfunction "VOA_7") (pintype "output"))
    )
    (net (code "28") (name "BH_R_PWM") (class "Default")
      (node (ref "BALL-HANDLE_RIGHT") (pin "3") (pinfunction "3_3") (pintype "passive"))
      (node (ref "U2") (pin "13") (pinfunction "VOB_13") (pintype "output"))
    )
    (net (code "29") (name "BH_R_PWM_3V") (class "Default")
      (node (ref "P8") (pin "19") (pinfunction "19_19") (pintype "passive"))
      (node (ref "U2") (pin "4") (pinfunction "VIB_4") (pintype "input"))
    )
    (net (code "30") (name "CANH") (class "Default")
      (node (ref "CAN") (pin "P$3") (pinfunction "P$3_P$3") (pintype "bidirectional"))
      (node (ref "SJ2") (pin "2") (pinfunction "2_2") (pintype "passive"))
      (node (ref "U$1") (pin "7") (pinfunction "CANH_7") (pintype "bidirectional"))
    )
    (net (code "31") (name "CANL") (class "Default")
      (node (ref "CAN") (pin "P$2") (pinfunction "P$2_P$2") (pintype "bidirectional"))
      (node (ref "R2") (pin "2") (pinfunction "2_2") (pintype "passive"))
      (node (ref "U$1") (pin "6") (pinfunction "CANL_6") (pintype "bidirectional"))
    )
    (net (code "32") (name "CAN_RX") (class "Default")
      (node (ref "LS_SPI") (pin "12") (pinfunction "B8_12") (pintype "bidirectional"))
      (node (ref "U$1") (pin "4") (pinfunction "RXD_4") (pintype "output"))
    )
    (net (code "33") (name "CAN_RX_3V") (class "Default")
      (node (ref "LS_SPI") (pin "9") (pinfunction "A8_9") (pintype "bidirectional"))
      (node (ref "P9") (pin "24") (pinfunction "24_24") (pintype "passive"))
    )
    (net (code "34") (name "CAN_TX") (class "Default")
      (node (ref "LS_SPI") (pin "13") (pinfunction "B7_13") (pintype "bidirectional"))
      (node (ref "U$1") (pin "1") (pinfunction "TXD_1") (pintype "input"))
    )
    (net (code "35") (name "CAN_TX_3V") (class "Default")
      (node (ref "LS_SPI") (pin "8") (pinfunction "A7_8") (pintype "bidirectional"))
      (node (ref "P9") (pin "26") (pinfunction "26_26") (pintype "passive"))
    )
    (net (code "36") (name "DRDY") (class "Default")
      (node (ref "CON_IMU2") (pin "3") (pinfunction "3_3") (pintype "passive"))
      (node (ref "P8") (pin "15") (pinfunction "15_15") (pintype "passive"))
    )
    (net (code "37") (name "GND") (class "Default")
      (node (ref "24V") (pin "C") (pinfunction "C_C") (pintype "passive"))
      (node (ref "5V1") (pin "C") (pinfunction "C_C") (pintype "passive"))
      (node (ref "5V2") (pin "C") (pinfunction "C_C") (pintype "passive"))
      (node (ref "ADC1") (pin "2") (pinfunction "2_2") (pintype "passive"))
      (node (ref "ADC2") (pin "2") (pinfunction "2_2") (pintype "passive"))
      (node (ref "ADC3") (pin "2") (pinfunction "2_2") (pintype "passive"))
      (node (ref "C1") (pin "2") (pinfunction "2_2") (pintype "passive"))
      (node (ref "C11") (pin "2") (pinfunction "2_2") (pintype "passive"))
      (node (ref "C13") (pin "1") (pinfunction "1_1") (pintype "passive"))
      (node (ref "C14") (pin "1") (pinfunction "1_1") (pintype "passive"))
      (node (ref "C18") (pin "-") (pinfunction "-_-") (pintype "passive"))
      (node (ref "C19") (pin "-") (pinfunction "-_-") (pintype "passive"))
      (node (ref "C2") (pin "2") (pinfunction "2_2") (pintype "passive"))
      (node (ref "C20") (pin "-") (pinfunction "-_-") (pintype "passive"))
      (node (ref "C3") (pin "2") (pinfunction "2_2") (pintype "passive"))
      (node (ref "C4") (pin "-") (pinfunction "-_-") (pintype "passive"))
      (node (ref "C5") (pin "-") (pinfunction "-_-") (pintype "passive"))
      (node (ref "C6") (pin "-") (pinfunction "-_-") (pintype "passive"))
      (node (ref "C7") (pin "2") (pinfunction "2_2") (pintype "passive"))
      (node (ref "C8") (pin "2") (pinfunction "2_2") (pintype "passive"))
      (node (ref "C9") (pin "2") (pinfunction "2_2") (pintype "passive"))
      (node (ref "CAN") (pin "P$4") (pinfunction "P$4_P$4") (pintype "bidirectional"))
      (node (ref "CON_IMU") (pin "3") (pinfunction "3_3") (pintype "passive"))
      (node (ref "CON_SPI-EXT") (pin "6") (pinfunction "6_6") (pintype "passive"))
      (node (ref "CON_STECKERBOX") (pin "1") (pinfunction "1_1") (pintype "passive"))
      (node (ref "CON_STECKERBOX") (pin "2") (pinfunction "2_2") (pintype "passive"))
      (node (ref "D6") (pin "A") (pinfunction "A_A") (pintype "passive"))
      (node (ref "D7") (pin "A") (pinfunction "A_A") (pintype "passive"))
      (node (ref "H1") (pin "B3,0") (pinfunction "MOUNT_B3,0") (pintype "passive"))
      (node (ref "H2") (pin "B3,0") (pinfunction "MOUNT_B3,0") (pintype "passive"))
      (node (ref "H3") (pin "B3,0") (pinfunction "MOUNT_B3,0") (pintype "passive"))
      (node (ref "H4") (pin "B3,0") (pinfunction "MOUNT_B3,0") (pintype "passive"))
      (node (ref "IC4") (pin "!EN") (pinfunction "~{EN}_!EN") (pintype "input"))
      (node (ref "IC4") (pin "GND") (pinfunction "GND_GND") (pintype "power_in"))
      (node (ref "IC5") (pin "!EN") (pinfunction "~{EN}_!EN") (pintype "input"))
      (node (ref "IC5") (pin "GND") (pinfunction "GND_GND") (pintype "power_in"))
      (node (ref "JP3") (pin "2") (pinfunction "2_2") (pintype "passive"))
      (node (ref "JP4") (pin "2") (pinfunction "2_2") (pintype "passive"))
      (node (ref "JST_CHASSIS") (pin "1") (pinfunction "1_1") (pintype "bidirectional"))
      (node (ref "JST_CHASSIS") (pin "3") (pinfunction "3_3") (pintype "bidirectional"))
      (node (ref "JST_CHASSIS") (pin "5") (pinfunction "5_5") (pintype "bidirectional"))
      (node (ref "JST_OPTICAL-FLOW") (pin "1") (pinfunction "1_1") (pintype "bidirectional"))
      (node (ref "LS_SPI") (pin "11") (pinfunction "GND_11") (pintype "passive"))
      (node (ref "NPN1") (pin "E") (pinfunction "E_E") (pintype "passive"))
      (node (ref "NPN2") (pin "E") (pinfunction "E_E") (pintype "passive"))
      (node (ref "NPN3") (pin "E") (pinfunction "E_E") (pintype "passive"))
      (node (ref "NPN4") (pin "E") (pinfunction "E_E") (pintype "passive"))
      (node (ref "P8") (pin "1") (pinfunction "1_1") (pintype "passive"))
      (node (ref "P8") (pin "2") (pinfunction "2_2") (pintype "passive"))
      (node (ref "P9") (pin "1") (pinfunction "1_1") (pintype "passive"))
      (node (ref "P9") (pin "2") (pinfunction "2_2") (pintype "passive"))
      (node (ref "P9") (pin "34") (pinfunction "34_34") (pintype "passive"))
      (node (ref "P9") (pin "43") (pinfunction "43_43") (pintype "passive"))
      (node (ref "P9") (pin "44") (pinfunction "44_44") (pintype "passive"))
      (node (ref "P9") (pin "45") (pinfunction "45_45") (pintype "passive"))
      (node (ref "P9") (pin "46") (pinfunction "46_46") (pintype "passive"))
      (node (ref "R1") (pin "1") (pinfunction "1_1") (pintype "passive"))
      (node (ref "R16") (pin "1") (pinfunction "1_1") (pintype "passive"))
      (node (ref "R17") (pin "1") (pinfunction "1_1") (pintype "passive"))
      (node (ref "R18") (pin "1") (pinfunction "1_1") (pintype "passive"))
      (node (ref "R19") (pin "1") (pinfunction "1_1") (pintype "passive"))
      (node (ref "R20") (pin "1") (pinfunction "1_1") (pintype "passive"))
      (node (ref "R21") (pin "1") (pinfunction "1_1") (pintype "passive"))
      (node (ref "R22") (pin "1") (pinfunction "1_1") (pintype "passive"))
      (node (ref "R3") (pin "1") (pinfunction "1_1") (pintype "passive"))
      (node (ref "SERVO1") (pin "1") (pinfunction "1_1") (pintype "passive"))
      (node (ref "SERVO2") (pin "1") (pinfunction "1_1") (pintype "passive"))
      (node (ref "U$1") (pin "2") (pinfunction "VSS_2") (pintype "passive"))
      (node (ref "U1") (pin "5") (pinfunction "GND2_5") (pintype "passive"))
      (node (ref "U2") (pin "2") (pinfunction "GND1_2") (pintype "passive"))
      (node (ref "U2") (pin "8") (pinfunction "GND1_2_8") (pintype "passive"))
      (node (ref "U3") (pin "5") (pinfunction "GND2_5") (pintype "passive"))
      (node (ref "U4") (pin "2") (pinfunction "GND1_2") (pintype "passive"))
      (node (ref "U4") (pin "8") (pinfunction "GND1_2_8") (pintype "passive"))
      (node (ref "X2") (pin "2") (pinfunction "KL_2") (pintype "passive"))
    )
    (net (code "38") (name "GND3") (class "Default")
      (node (ref "5V3") (pin "C") (pinfunction "C_C") (pintype "passive"))
      (node (ref "BALL-HANDLE_LEFT") (pin "1") (pinfunction "1_1") (pintype "passive"))
      (node (ref "BALL-HANDLE_RIGHT") (pin "1") (pinfunction "1_1") (pintype "passive"))
      (node (ref "C10") (pin "2") (pinfunction "2_2") (pintype "passive"))
      (node (ref "C16") (pin "2") (pinfunction "2_2") (pintype "passive"))
      (node (ref "C17") (pin "2") (pinfunction "2_2") (pintype "passive"))
      (node (ref "IC3") (pin "4") (pinfunction "GND_4") (pintype "passive"))
      (node (ref "U1") (pin "4") (pinfunction "GND1_4") (pintype "passive"))
      (node (ref "U2") (pin "15") (pinfunction "GND2_2_15") (pintype "passive"))
      (node (ref "U2") (pin "9") (pinfunction "GND2_9") (pintype "passive"))
      (node (ref "U3") (pin "4") (pinfunction "GND1_4") (pintype "passive"))
      (node (ref "U4") (pin "15") (pinfunction "GND2_2_15") (pintype "passive"))
      (node (ref "U4") (pin "9") (pinfunction "GND2_9") (pintype "passive"))
    )
    (net (code "39") (name "I2C2_SCL") (class "Default")
      (node (ref "CON_IMU") (pin "4") (pinfunction "4_4") (pintype "passive"))
      (node (ref "P9") (pin "19") (pinfunction "19_19") (pintype "passive"))
      (node (ref "R27") (pin "1") (pinfunction "1_1") (pintype "passive"))
      (node (ref "R29") (pin "1") (pinfunction "1_1") (pintype "passive"))
    )
    (net (code "40") (name "I2C2_SDA") (class "Default")
      (node (ref "CON_IMU") (pin "5") (pinfunction "5_5") (pintype "passive"))
      (node (ref "P9") (pin "20") (pinfunction "20_20") (pintype "passive"))
      (node (ref "R28") (pin "1") (pinfunction "1_1") (pintype "passive"))
      (node (ref "R30") (pin "1") (pinfunction "1_1") (pintype "passive"))
    )
    (net (code "41") (name "INT1") (class "Default")
      (node (ref "CON_IMU2") (pin "4") (pinfunction "4_4") (pintype "passive"))
      (node (ref "P8") (pin "17") (pinfunction "17_17") (pintype "passive"))
    )
    (net (code "42") (name "INT2") (class "Default")
      (node (ref "CON_IMU2") (pin "5") (pinfunction "5_5") (pintype "passive"))
      (node (ref "P8") (pin "26") (pinfunction "26_26") (pintype "passive"))
    )
    (net (code "43") (name "INTG") (class "Default")
      (node (ref "CON_IMU2") (pin "2") (pinfunction "2_2") (pintype "passive"))
      (node (ref "P8") (pin "11") (pinfunction "11_11") (pintype "passive"))
    )
    (net (code "44") (name "LB_ADC") (class "Default")
      (node (ref "JST_CHASSIS") (pin "4") (pinfunction "4_4") (pintype "bidirectional"))
      (node (ref "R23") (pin "2") (pinfunction "2_2") (pintype "passive"))
    )
    (net (code "45") (name "Net-(5V1-PadA)") (class "Default")
      (node (ref "5V1") (pin "A") (pinfunction "A_A") (pintype "passive"))
      (node (ref "R6") (pin "1") (pinfunction "1_1") (pintype "passive"))
    )
    (net (code "46") (name "Net-(5V2-PadA)") (class "Default")
      (node (ref "5V2") (pin "A") (pinfunction "A_A") (pintype "passive"))
      (node (ref "R7") (pin "1") (pinfunction "1_1") (pintype "passive"))
    )
    (net (code "47") (name "Net-(5V3-PadA)") (class "Default")
      (node (ref "5V3") (pin "A") (pinfunction "A_A") (pintype "passive"))
      (node (ref "R8") (pin "1") (pinfunction "1_1") (pintype "passive"))
    )
    (net (code "48") (name "Net-(24V-PadA)") (class "Default")
      (node (ref "24V") (pin "A") (pinfunction "A_A") (pintype "passive"))
      (node (ref "R5") (pin "1") (pinfunction "1_1") (pintype "passive"))
    )
    (net (code "49") (name "Net-(BALL-HANDLE_LEFT-Pad8)") (class "Default")
      (node (ref "BALL-HANDLE_LEFT") (pin "8") (pinfunction "8_8") (pintype "passive"))
      (node (ref "D9") (pin "A") (pinfunction "A_A") (pintype "passive"))
    )
    (net (code "50") (name "Net-(BALL-HANDLE_RIGHT-Pad8)") (class "Default")
      (node (ref "BALL-HANDLE_RIGHT") (pin "8") (pinfunction "8_8") (pintype "passive"))
      (node (ref "D8") (pin "A") (pinfunction "A_A") (pintype "passive"))
    )
    (net (code "51") (name "Net-(CAN-PadP$1)") (class "Default")
      (node (ref "CAN") (pin "P$1") (pinfunction "P$1_P$1") (pintype "bidirectional"))
      (node (ref "SJ1") (pin "1") (pinfunction "1_1") (pintype "passive"))
    )
    (net (code "52") (name "Net-(D6-PadC)") (class "Default")
      (node (ref "D6") (pin "C") (pinfunction "C_C") (pintype "passive"))
      (node (ref "IC5") (pin "OUT") (pinfunction "OUT_OUT") (pintype "output"))
      (node (ref "L1") (pin "P$1") (pinfunction "P$1_P$1") (pintype "bidirectional"))
    )
    (net (code "53") (name "Net-(D7-PadC)") (class "Default")
      (node (ref "D7") (pin "C") (pinfunction "C_C") (pintype "passive"))
      (node (ref "IC4") (pin "OUT") (pinfunction "OUT_OUT") (pintype "output"))
      (node (ref "L2") (pin "P$1") (pinfunction "P$1_P$1") (pintype "bidirectional"))
    )
    (net (code "54") (name "Net-(I2C-Pad1)") (class "Default")
      (node (ref "I2C") (pin "1") (pinfunction "1_1") (pintype "passive"))
      (node (ref "R29") (pin "2") (pinfunction "2_2") (pintype "passive"))
    )
    (net (code "55") (name "Net-(I2C-Pad2)") (class "Default")
      (node (ref "I2C") (pin "2") (pinfunction "2_2") (pintype "passive"))
      (node (ref "R30") (pin "2") (pinfunction "2_2") (pintype "passive"))
    )
    (net (code "56") (name "Net-(JST_CHASSIS-Pad6)") (class "Default")
      (node (ref "JST_CHASSIS") (pin "6") (pinfunction "6_6") (pintype "bidirectional"))
      (node (ref "R9") (pin "2") (pinfunction "2_2") (pintype "passive"))
    )
    (net (code "57") (name "Net-(NPN1-PadB)") (class "Default")
      (node (ref "NPN1") (pin "B") (pinfunction "B_B") (pintype "passive"))
      (node (ref "R32") (pin "1") (pinfunction "1_1") (pintype "passive"))
    )
    (net (code "58") (name "Net-(NPN1-PadC)") (class "Default")
      (node (ref "NPN1") (pin "C") (pinfunction "C_C") (pintype "passive"))
      (node (ref "R10") (pin "2") (pinfunction "2_2") (pintype "passive"))
      (node (ref "R13") (pin "1") (pinfunction "1_1") (pintype "passive"))
    )
    (net (code "59") (name "Net-(NPN2-PadB)") (class "Default")
      (node (ref "NPN2") (pin "B") (pinfunction "B_B") (pintype "passive"))
      (node (ref "R33") (pin "1") (pinfunction "1_1") (pintype "passive"))
    )
    (net (code "60") (name "Net-(NPN2-PadC)") (class "Default")
      (node (ref "NPN2") (pin "C") (pinfunction "C_C") (pintype "passive"))
      (node (ref "R11") (pin "2") (pinfunction "2_2") (pintype "passive"))
      (node (ref "R14") (pin "1") (pinfunction "1_1") (pintype "passive"))
    )
    (net (code "61") (name "Net-(NPN3-PadB)") (class "Default")
      (node (ref "NPN3") (pin "B") (pinfunction "B_B") (pintype "passive"))
      (node (ref "R34") (pin "1") (pinfunction "1_1") (pintype "passive"))
    )
    (net (code "62") (name "Net-(NPN3-PadC)") (class "Default")
      (node (ref "NPN3") (pin "C") (pinfunction "C_C") (pintype "passive"))
      (node (ref "R12") (pin "2") (pinfunction "2_2") (pintype "passive"))
      (node (ref "R15") (pin "1") (pinfunction "1_1") (pintype "passive"))
    )
    (net (code "63") (name "Net-(NPN4-PadB)") (class "Default")
      (node (ref "NPN4") (pin "B") (pinfunction "B_B") (pintype "passive"))
      (node (ref "R35") (pin "1") (pinfunction "1_1") (pintype "passive"))
    )
    (net (code "64") (name "Net-(NPN4-PadC)") (class "Default")
      (node (ref "NPN4") (pin "C") (pinfunction "C_C") (pintype "passive"))
      (node (ref "R31") (pin "2") (pinfunction "2_2") (pintype "passive"))
      (node (ref "R4") (pin "1") (pinfunction "1_1") (pintype "passive"))
    )
    (net (code "65") (name "Net-(PNP1-PadB)") (class "Default")
      (node (ref "PNP1") (pin "B") (pinfunction "B_B") (pintype "passive"))
      (node (ref "R10") (pin "1") (pinfunction "1_1") (pintype "passive"))
    )
    (net (code "66") (name "Net-(PNP2-PadB)") (class "Default")
      (node (ref "PNP2") (pin "B") (pinfunction "B_B") (pintype "passive"))
      (node (ref "R11") (pin "1") (pinfunction "1_1") (pintype "passive"))
    )
    (net (code "67") (name "Net-(PNP3-PadB)") (class "Default")
      (node (ref "PNP3") (pin "B") (pinfunction "B_B") (pintype "passive"))
      (node (ref "R12") (pin "1") (pinfunction "1_1") (pintype "passive"))
    )
    (net (code "68") (name "Net-(PNP4-PadB)") (class "Default")
      (node (ref "PNP4") (pin "B") (pinfunction "B_B") (pintype "passive"))
      (node (ref "R31") (pin "1") (pinfunction "1_1") (pintype "passive"))
    )
    (net (code "69") (name "Net-(R2-Pad1)") (class "Default")
      (node (ref "R2") (pin "1") (pinfunction "1_1") (pintype "passive"))
      (node (ref "SJ2") (pin "1") (pinfunction "1_1") (pintype "passive"))
    )
    (net (code "70") (name "Net-(U$1-RS)") (class "Default")
      (node (ref "R1") (pin "2") (pinfunction "2_2") (pintype "passive"))
      (node (ref "U$1") (pin "8") (pinfunction "RS_8") (pintype "input"))
    )
    (net (code "71") (name "Net-(X2A-KL)") (class "Default")
      (node (ref "D5") (pin "A") (pinfunction "A_A") (pintype "passive"))
      (node (ref "X2") (pin "1") (pinfunction "KL_1") (pintype "passive"))
    )
    (net (code "72") (name "OF_LED") (class "Default")
      (node (ref "PNP4") (pin "C") (pinfunction "C_C") (pintype "passive"))
      (node (ref "R9") (pin "1") (pinfunction "1_1") (pintype "passive"))
    )
    (net (code "73") (name "OF_LED_3V") (class "Default")
      (node (ref "P9") (pin "12") (pinfunction "12_12") (pintype "passive"))
      (node (ref "R3") (pin "2") (pinfunction "2_2") (pintype "passive"))
      (node (ref "R35") (pin "2") (pinfunction "2_2") (pintype "passive"))
    )
    (net (code "74") (name "OF_NCS_3V") (class "Default")
      (node (ref "JST_OPTICAL-FLOW") (pin "3") (pinfunction "3_3") (pintype "bidirectional"))
      (node (ref "P9") (pin "30") (pinfunction "30_30") (pintype "passive"))
    )
    (net (code "75") (name "OF_NPD_3V") (class "Default")
      (node (ref "JST_OPTICAL-FLOW") (pin "5") (pinfunction "5_5") (pintype "bidirectional"))
      (node (ref "P9") (pin "25") (pinfunction "25_25") (pintype "passive"))
    )
    (net (code "76") (name "OF_RST_3V") (class "Default")
      (node (ref "JST_OPTICAL-FLOW") (pin "7") (pinfunction "7_7") (pintype "bidirectional"))
      (node (ref "P9") (pin "27") (pinfunction "27_27") (pintype "passive"))
    )
    (net (code "77") (name "SERVO_PWM") (class "Default")
      (node (ref "LS_SPI") (pin "14") (pinfunction "B6_14") (pintype "bidirectional"))
      (node (ref "SERVO1") (pin "3") (pinfunction "3_3") (pintype "passive"))
    )
    (net (code "78") (name "SERVO_PWM2") (class "Default")
      (node (ref "LS_SPI") (pin "15") (pinfunction "B5_15") (pintype "bidirectional"))
      (node (ref "SERVO2") (pin "3") (pinfunction "3_3") (pintype "passive"))
    )
    (net (code "79") (name "SERVO_PWM2_3V") (class "Default")
      (node (ref "LS_SPI") (pin "6") (pinfunction "A5_6") (pintype "bidirectional"))
      (node (ref "P9") (pin "16") (pinfunction "16_16") (pintype "passive"))
    )
    (net (code "80") (name "SERVO_PWM_3V") (class "Default")
      (node (ref "LS_SPI") (pin "7") (pinfunction "A6_7") (pintype "bidirectional"))
      (node (ref "P9") (pin "14") (pinfunction "14_14") (pintype "passive"))
    )
    (net (code "81") (name "SPI0_CLK") (class "Default")
      (node (ref "JST_OPTICAL-FLOW") (pin "6") (pinfunction "6_6") (pintype "bidirectional"))
      (node (ref "LS_SPI") (pin "5") (pinfunction "A4_5") (pintype "bidirectional"))
      (node (ref "P9") (pin "22") (pinfunction "22_22") (pintype "passive"))
    )
    (net (code "82") (name "SPI0_CS") (class "Default")
      (node (ref "LS_SPI") (pin "1") (pinfunction "A1_1") (pintype "bidirectional"))
      (node (ref "P9") (pin "17") (pinfunction "17_17") (pintype "passive"))
    )
    (net (code "83") (name "SPI0_D0_MISO") (class "Default")
      (node (ref "JST_OPTICAL-FLOW") (pin "4") (pinfunction "4_4") (pintype "bidirectional"))
      (node (ref "LS_SPI") (pin "4") (pinfunction "A3_4") (pintype "bidirectional"))
      (node (ref "P9") (pin "21") (pinfunction "21_21") (pintype "passive"))
    )
    (net (code "84") (name "SPI0_D1_MOSI") (class "Default")
      (node (ref "JST_OPTICAL-FLOW") (pin "2") (pinfunction "2_2") (pintype "bidirectional"))
      (node (ref "LS_SPI") (pin "3") (pinfunction "A2_3") (pintype "bidirectional"))
      (node (ref "P9") (pin "18") (pinfunction "18_18") (pintype "passive"))
    )
    (net (code "85") (name "SPI_CLK") (class "Default")
      (node (ref "CON_SPI-EXT") (pin "3") (pinfunction "3_3") (pintype "passive"))
      (node (ref "LS_SPI") (pin "16") (pinfunction "B4_16") (pintype "bidirectional"))
    )
    (net (code "86") (name "SPI_CS") (class "Default")
      (node (ref "CON_SPI-EXT") (pin "5") (pinfunction "5_5") (pintype "passive"))
      (node (ref "LS_SPI") (pin "20") (pinfunction "B1_20") (pintype "bidirectional"))
    )
    (net (code "87") (name "SPI_MISO") (class "Default")
      (node (ref "CON_SPI-EXT") (pin "1") (pinfunction "1_1") (pintype "passive"))
      (node (ref "LS_SPI") (pin "17") (pinfunction "B3_17") (pintype "bidirectional"))
    )
    (net (code "88") (name "SPI_MOSI") (class "Default")
      (node (ref "CON_SPI-EXT") (pin "4") (pinfunction "4_4") (pintype "passive"))
      (node (ref "LS_SPI") (pin "18") (pinfunction "B2_18") (pintype "bidirectional"))
    )
    (net (code "89") (name "SW_BUNDLE-LED") (class "Default")
      (node (ref "CON_STECKERBOX") (pin "8") (pinfunction "8_8") (pintype "passive"))
      (node (ref "PNP2") (pin "C") (pinfunction "C_C") (pintype "passive"))
    )
    (net (code "90") (name "SW_BUNDLE-LED_3V") (class "Default")
      (node (ref "P9") (pin "41") (pinfunction "41_41") (pintype "passive"))
      (node (ref "R17") (pin "2") (pinfunction "2_2") (pintype "passive"))
      (node (ref "R33") (pin "2") (pinfunction "2_2") (pintype "passive"))
    )
    (net (code "91") (name "SW_BUNDLE_3V") (class "Default")
      (node (ref "CON_STECKERBOX") (pin "7") (pinfunction "7_7") (pintype "passive"))
      (node (ref "P9") (pin "13") (pinfunction "13_13") (pintype "passive"))
    )
    (net (code "92") (name "SW_POWER-LED") (class "Default")
      (node (ref "CON_STECKERBOX") (pin "10") (pinfunction "10_10") (pintype "passive"))
      (node (ref "PNP3") (pin "C") (pinfunction "C_C") (pintype "passive"))
    )
    (net (code "93") (name "SW_POWER-LED_3V") (class "Default")
      (node (ref "P9") (pin "23") (pinfunction "23_23") (pintype "passive"))
      (node (ref "R16") (pin "2") (pinfunction "2_2") (pintype "passive"))
      (node (ref "R34") (pin "2") (pinfunction "2_2") (pintype "passive"))
    )
    (net (code "94") (name "SW_PWR_BUT") (class "Default")
      (node (ref "CON_STECKERBOX") (pin "9") (pinfunction "9_9") (pintype "passive"))
      (node (ref "P9") (pin "9") (pinfunction "9_9") (pintype "passive"))
    )
    (net (code "95") (name "SW_VISION-LED") (class "Default")
      (node (ref "CON_STECKERBOX") (pin "6") (pinfunction "6_6") (pintype "passive"))
      (node (ref "PNP1") (pin "C") (pinfunction "C_C") (pintype "passive"))
    )
    (net (code "96") (name "SW_VISION-LED_3V") (class "Default")
      (node (ref "P9") (pin "42") (pinfunction "42_42") (pintype "passive"))
      (node (ref "R18") (pin "2") (pinfunction "2_2") (pintype "passive"))
      (node (ref "R32") (pin "2") (pinfunction "2_2") (pintype "passive"))
    )
    (net (code "97") (name "SW_VISION_3V") (class "Default")
      (node (ref "CON_STECKERBOX") (pin "5") (pinfunction "5_5") (pintype "passive"))
      (node (ref "P9") (pin "11") (pinfunction "11_11") (pintype "passive"))
    )
    (net (code "98") (name "unconnected-(BALL-HANDLE_LEFT-Pad7)") (class "Default")
      (node (ref "BALL-HANDLE_LEFT") (pin "7") (pinfunction "7_7") (pintype "passive"))
    )
    (net (code "99") (name "unconnected-(BALL-HANDLE_RIGHT-Pad7)") (class "Default")
      (node (ref "BALL-HANDLE_RIGHT") (pin "7") (pinfunction "7_7") (pintype "passive"))
    )
    (net (code "100") (name "unconnected-(CON_IMU-Pad2)") (class "Default")
      (node (ref "CON_IMU") (pin "2") (pinfunction "2_2") (pintype "passive"))
    )
    (net (code "101") (name "unconnected-(CON_IMU-Pad6)") (class "Default")
      (node (ref "CON_IMU") (pin "6") (pinfunction "6_6") (pintype "passive"))
    )
    (net (code "102") (name "unconnected-(CON_IMU-Pad7)") (class "Default")
      (node (ref "CON_IMU") (pin "7") (pinfunction "7_7") (pintype "passive"))
    )
    (net (code "103") (name "unconnected-(CON_IMU-Pad8)") (class "Default")
      (node (ref "CON_IMU") (pin "8") (pinfunction "8_8") (pintype "passive"))
    )
    (net (code "104") (name "unconnected-(CON_IMU-Pad9)") (class "Default")
      (node (ref "CON_IMU") (pin "9") (pinfunction "9_9") (pintype "passive"))
    )
    (net (code "105") (name "unconnected-(CON_IMU2-Pad1)") (class "Default")
      (node (ref "CON_IMU2") (pin "1") (pinfunction "1_1") (pintype "passive"))
    )
    (net (code "106") (name "unconnected-(CON_STECKERBOX-Pad3)") (class "Default")
      (node (ref "CON_STECKERBOX") (pin "3") (pinfunction "3_3") (pintype "passive"))
    )
    (net (code "107") (name "unconnected-(CON_STECKERBOX-Pad4)") (class "Default")
      (node (ref "CON_STECKERBOX") (pin "4") (pinfunction "4_4") (pintype "passive"))
    )
    (net (code "108") (name "unconnected-(JST_CHASSIS-Pad2)") (class "Default")
      (node (ref "JST_CHASSIS") (pin "2") (pinfunction "2_2") (pintype "bidirectional"))
    )
    (net (code "109") (name "unconnected-(P8-Pad3)") (class "Default")
      (node (ref "P8") (pin "3") (pinfunction "3_3") (pintype "passive"))
    )
    (net (code "110") (name "unconnected-(P8-Pad4)") (class "Default")
      (node (ref "P8") (pin "4") (pinfunction "4_4") (pintype "passive"))
    )
    (net (code "111") (name "unconnected-(P8-Pad5)") (class "Default")
      (node (ref "P8") (pin "5") (pinfunction "5_5") (pintype "passive"))
    )
    (net (code "112") (name "unconnected-(P8-Pad6)") (class "Default")
      (node (ref "P8") (pin "6") (pinfunction "6_6") (pintype "passive"))
    )
    (net (code "113") (name "unconnected-(P8-Pad20)") (class "Default")
      (node (ref "P8") (pin "20") (pinfunction "20_20") (pintype "passive"))
    )
    (net (code "114") (name "unconnected-(P8-Pad21)") (class "Default")
      (node (ref "P8") (pin "21") (pinfunction "21_21") (pintype "passive"))
    )
    (net (code "115") (name "unconnected-(P8-Pad22)") (class "Default")
      (node (ref "P8") (pin "22") (pinfunction "22_22") (pintype "passive"))
    )
    (net (code "116") (name "unconnected-(P8-Pad23)") (class "Default")
      (node (ref "P8") (pin "23") (pinfunction "23_23") (pintype "passive"))
    )
    (net (code "117") (name "unconnected-(P8-Pad24)") (class "Default")
      (node (ref "P8") (pin "24") (pinfunction "24_24") (pintype "passive"))
    )
    (net (code "118") (name "unconnected-(P8-Pad25)") (class "Default")
      (node (ref "P8") (pin "25") (pinfunction "25_25") (pintype "passive"))
    )
    (net (code "119") (name "unconnected-(P8-Pad27)") (class "Default")
      (node (ref "P8") (pin "27") (pinfunction "27_27") (pintype "passive"))
    )
    (net (code "120") (name "unconnected-(P8-Pad28)") (class "Default")
      (node (ref "P8") (pin "28") (pinfunction "28_28") (pintype "passive"))
    )
    (net (code "121") (name "unconnected-(P8-Pad29)") (class "Default")
      (node (ref "P8") (pin "29") (pinfunction "29_29") (pintype "passive"))
    )
    (net (code "122") (name "unconnected-(P8-Pad30)") (class "Default")
      (node (ref "P8") (pin "30") (pinfunction "30_30") (pintype "passive"))
    )
    (net (code "123") (name "unconnected-(P8-Pad31)") (class "Default")
      (node (ref "P8") (pin "31") (pinfunction "31_31") (pintype "passive"))
    )
    (net (code "124") (name "unconnected-(P8-Pad32)") (class "Default")
      (node (ref "P8") (pin "32") (pinfunction "32_32") (pintype "passive"))
    )
    (net (code "125") (name "unconnected-(P8-Pad33)") (class "Default")
      (node (ref "P8") (pin "33") (pinfunction "33_33") (pintype "passive"))
    )
    (net (code "126") (name "unconnected-(P8-Pad34)") (class "Default")
      (node (ref "P8") (pin "34") (pinfunction "34_34") (pintype "passive"))
    )
    (net (code "127") (name "unconnected-(P8-Pad35)") (class "Default")
      (node (ref "P8") (pin "35") (pinfunction "35_35") (pintype "passive"))
    )
    (net (code "128") (name "unconnected-(P8-Pad36)") (class "Default")
      (node (ref "P8") (pin "36") (pinfunction "36_36") (pintype "passive"))
    )
    (net (code "129") (name "unconnected-(P8-Pad37)") (class "Default")
      (node (ref "P8") (pin "37") (pinfunction "37_37") (pintype "passive"))
    )
    (net (code "130") (name "unconnected-(P8-Pad38)") (class "Default")
      (node (ref "P8") (pin "38") (pinfunction "38_38") (pintype "passive"))
    )
    (net (code "131") (name "unconnected-(P8-Pad39)") (class "Default")
      (node (ref "P8") (pin "39") (pinfunction "39_39") (pintype "passive"))
    )
    (net (code "132") (name "unconnected-(P8-Pad40)") (class "Default")
      (node (ref "P8") (pin "40") (pinfunction "40_40") (pintype "passive"))
    )
    (net (code "133") (name "unconnected-(P8-Pad41)") (class "Default")
      (node (ref "P8") (pin "41") (pinfunction "41_41") (pintype "passive"))
    )
    (net (code "134") (name "unconnected-(P8-Pad42)") (class "Default")
      (node (ref "P8") (pin "42") (pinfunction "42_42") (pintype "passive"))
    )
    (net (code "135") (name "unconnected-(P8-Pad43)") (class "Default")
      (node (ref "P8") (pin "43") (pinfunction "43_43") (pintype "passive"))
    )
    (net (code "136") (name "unconnected-(P8-Pad44)") (class "Default")
      (node (ref "P8") (pin "44") (pinfunction "44_44") (pintype "passive"))
    )
    (net (code "137") (name "unconnected-(P8-Pad45)") (class "Default")
      (node (ref "P8") (pin "45") (pinfunction "45_45") (pintype "passive"))
    )
    (net (code "138") (name "unconnected-(P8-Pad46)") (class "Default")
      (node (ref "P8") (pin "46") (pinfunction "46_46") (pintype "passive"))
    )
    (net (code "139") (name "unconnected-(P9-Pad7)") (class "Default")
      (node (ref "P9") (pin "7") (pinfunction "7_7") (pintype "passive"))
    )
    (net (code "140") (name "unconnected-(P9-Pad8)") (class "Default")
      (node (ref "P9") (pin "8") (pinfunction "8_8") (pintype "passive"))
    )
    (net (code "141") (name "unconnected-(P9-Pad10)") (class "Default")
      (node (ref "P9") (pin "10") (pinfunction "10_10") (pintype "passive"))
    )
    (net (code "142") (name "unconnected-(P9-Pad15)") (class "Default")
      (node (ref "P9") (pin "15") (pinfunction "15_15") (pintype "passive"))
    )
    (net (code "143") (name "unconnected-(P9-Pad28)") (class "Default")
      (node (ref "P9") (pin "28") (pinfunction "28_28") (pintype "passive"))
    )
    (net (code "144") (name "unconnected-(P9-Pad29)") (class "Default")
      (node (ref "P9") (pin "29") (pinfunction "29_29") (pintype "passive"))
    )
    (net (code "145") (name "unconnected-(P9-Pad31)") (class "Default")
      (node (ref "P9") (pin "31") (pinfunction "31_31") (pintype "passive"))
    )
    (net (code "146") (name "unconnected-(P9-Pad32)") (class "Default")
      (node (ref "P9") (pin "32") (pinfunction "32_32") (pintype "passive"))
    )
    (net (code "147") (name "unconnected-(P9-Pad33)") (class "Default")
      (node (ref "P9") (pin "33") (pinfunction "33_33") (pintype "passive"))
    )
    (net (code "148") (name "unconnected-(P9-Pad35)") (class "Default")
      (node (ref "P9") (pin "35") (pinfunction "35_35") (pintype "passive"))
    )
    (net (code "149") (name "unconnected-(P9-Pad36)") (class "Default")
      (node (ref "P9") (pin "36") (pinfunction "36_36") (pintype "passive"))
    )
    (net (code "150") (name "unconnected-(U$1-VREF-Pad5)") (class "Default")
      (node (ref "U$1") (pin "5") (pinfunction "VREF_5") (pintype "output"))
    )
    (net (code "151") (name "unconnected-(U2-NC-Pad11)") (class "Default")
      (node (ref "U2") (pin "11") (pinfunction "NC_11") (pintype "no_connect"))
    )
    (net (code "152") (name "unconnected-(U2-NC_2-Pad6)") (class "Default")
      (node (ref "U2") (pin "6") (pinfunction "NC_2_6") (pintype "no_connect"))
    )
    (net (code "153") (name "unconnected-(U2-NC_3-Pad7)") (class "Default")
      (node (ref "U2") (pin "7") (pinfunction "NC_3_7") (pintype "no_connect"))
    )
    (net (code "154") (name "unconnected-(U2-VE2-Pad10)") (class "Default")
      (node (ref "U2") (pin "10") (pinfunction "VE2_10") (pintype "input"))
    )
    (net (code "155") (name "unconnected-(U4-NC-Pad11)") (class "Default")
      (node (ref "U4") (pin "11") (pinfunction "NC_11") (pintype "no_connect"))
    )
    (net (code "156") (name "unconnected-(U4-NC_2-Pad6)") (class "Default")
      (node (ref "U4") (pin "6") (pinfunction "NC_2_6") (pintype "no_connect"))
    )
    (net (code "157") (name "unconnected-(U4-NC_3-Pad7)") (class "Default")
      (node (ref "U4") (pin "7") (pinfunction "NC_3_7") (pintype "no_connect"))
    )
    (net (code "158") (name "unconnected-(U4-VE2-Pad10)") (class "Default")
      (node (ref "U4") (pin "10") (pinfunction "VE2_10") (pintype "input"))
    )
    (net (code "159") (name "~{BH_L_RESET_3V}") (class "Default")
      (node (ref "P8") (pin "8") (pinfunction "8_8") (pintype "passive"))
      (node (ref "U4") (pin "5") (pinfunction "VIC_5") (pintype "input"))
    )
    (net (code "160") (name "~{BH_L_RESET}") (class "Default")
      (node (ref "BALL-HANDLE_LEFT") (pin "4") (pinfunction "4_4") (pintype "passive"))
      (node (ref "U4") (pin "12") (pinfunction "VOC_12") (pintype "output"))
    )
    (net (code "161") (name "~{BH_R_RESET_3V}") (class "Default")
      (node (ref "P8") (pin "10") (pinfunction "10_10") (pintype "passive"))
      (node (ref "U2") (pin "5") (pinfunction "VIC_5") (pintype "input"))
    )
    (net (code "162") (name "~{BH_R_RESET}") (class "Default")
      (node (ref "BALL-HANDLE_RIGHT") (pin "4") (pinfunction "4_4") (pintype "passive"))
      (node (ref "U2") (pin "12") (pinfunction "VOC_12") (pintype "output"))
    )
  )
)
